# marbles_v70.net
KiCad netlist of a schematic drawn in EAGLE
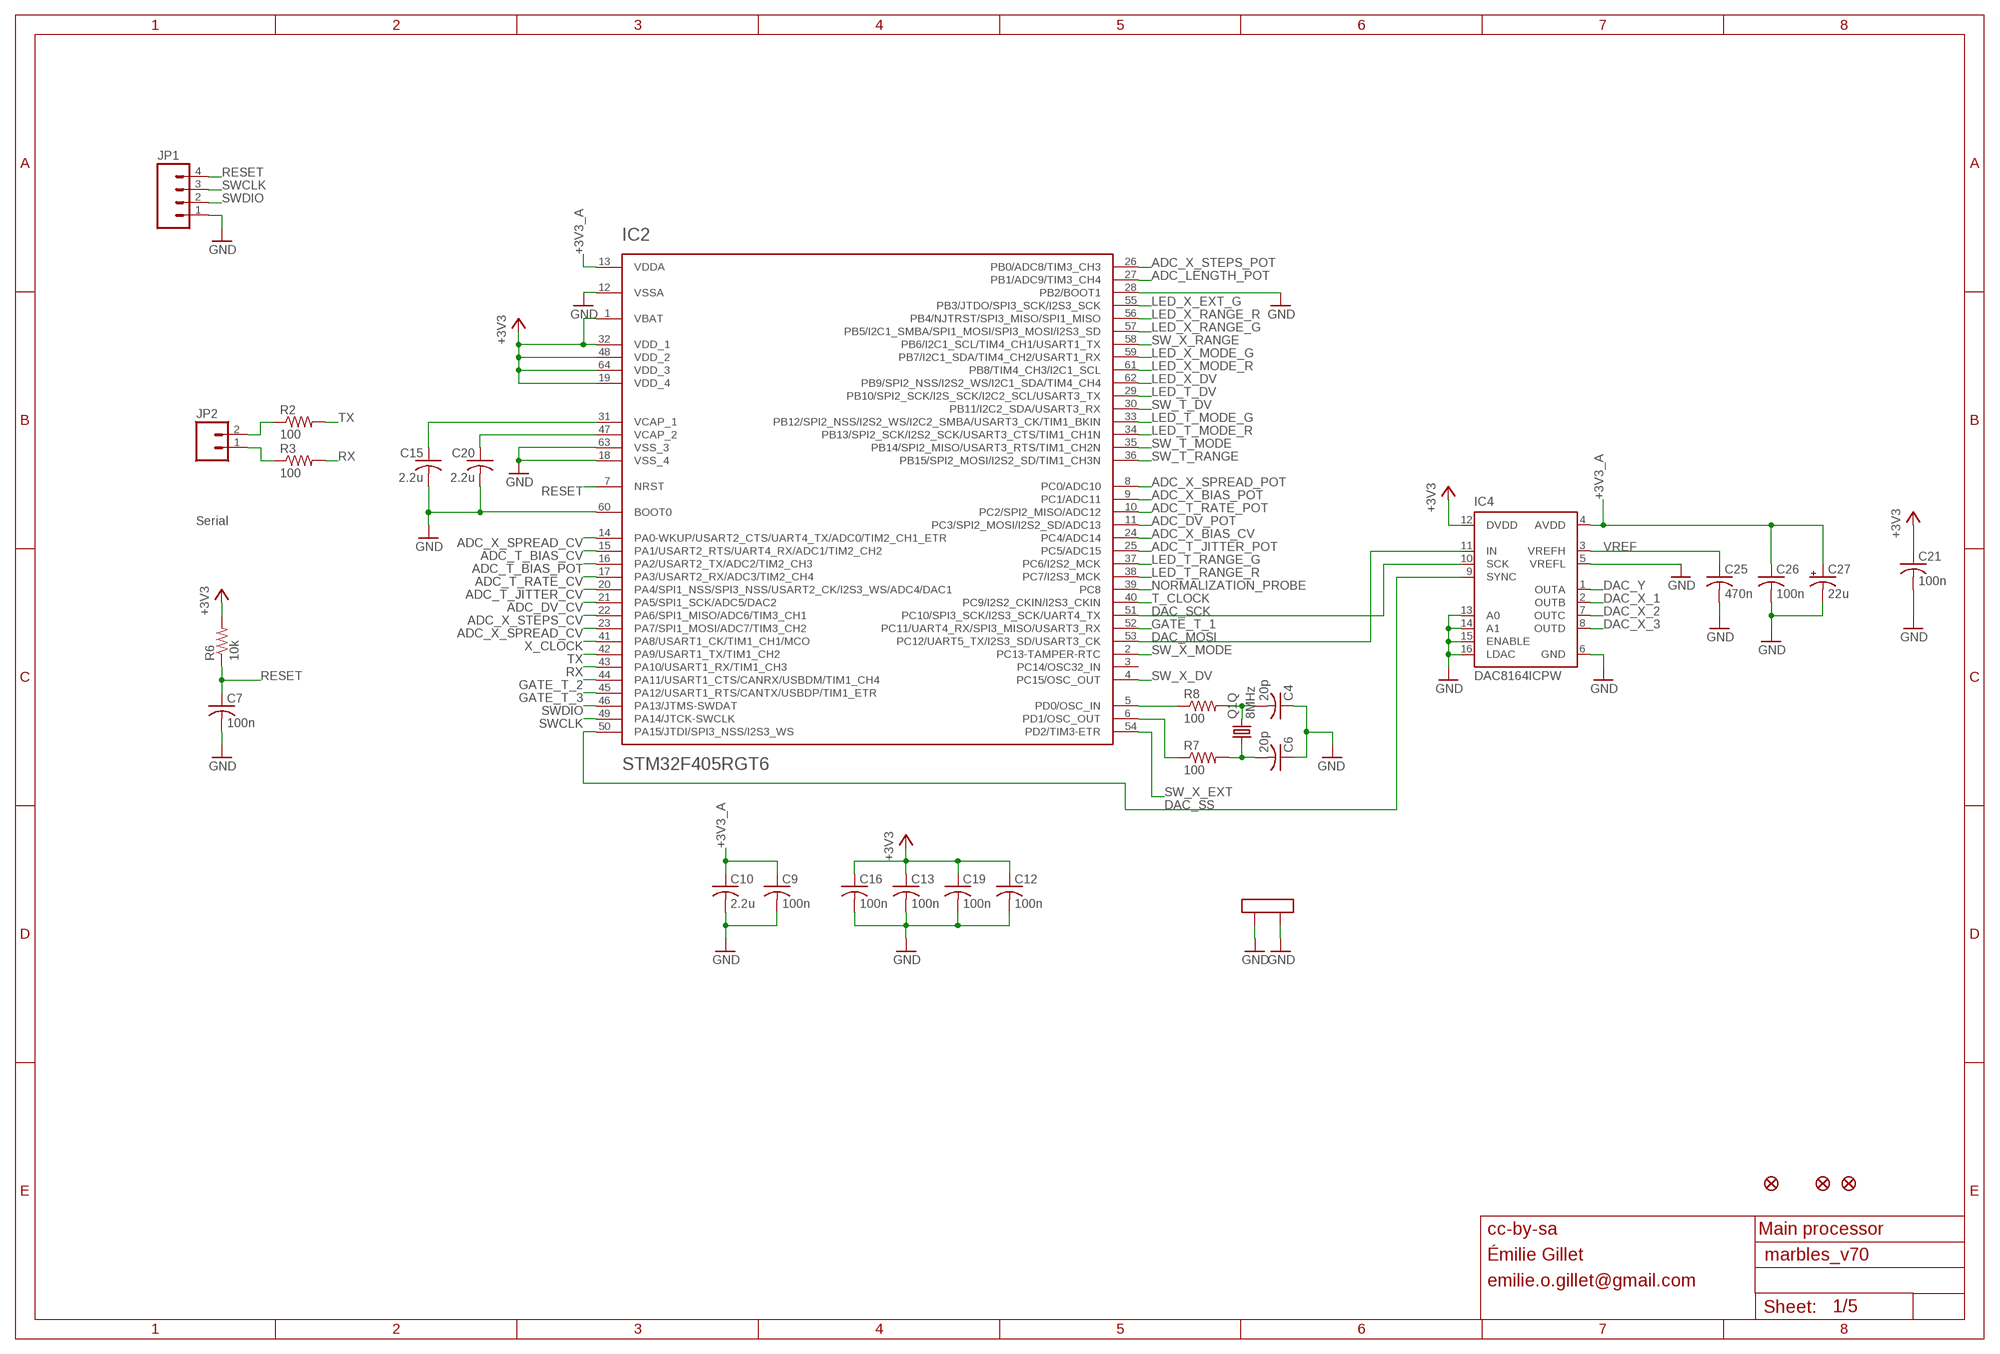
[diagram p0: schematic, sheet 1]
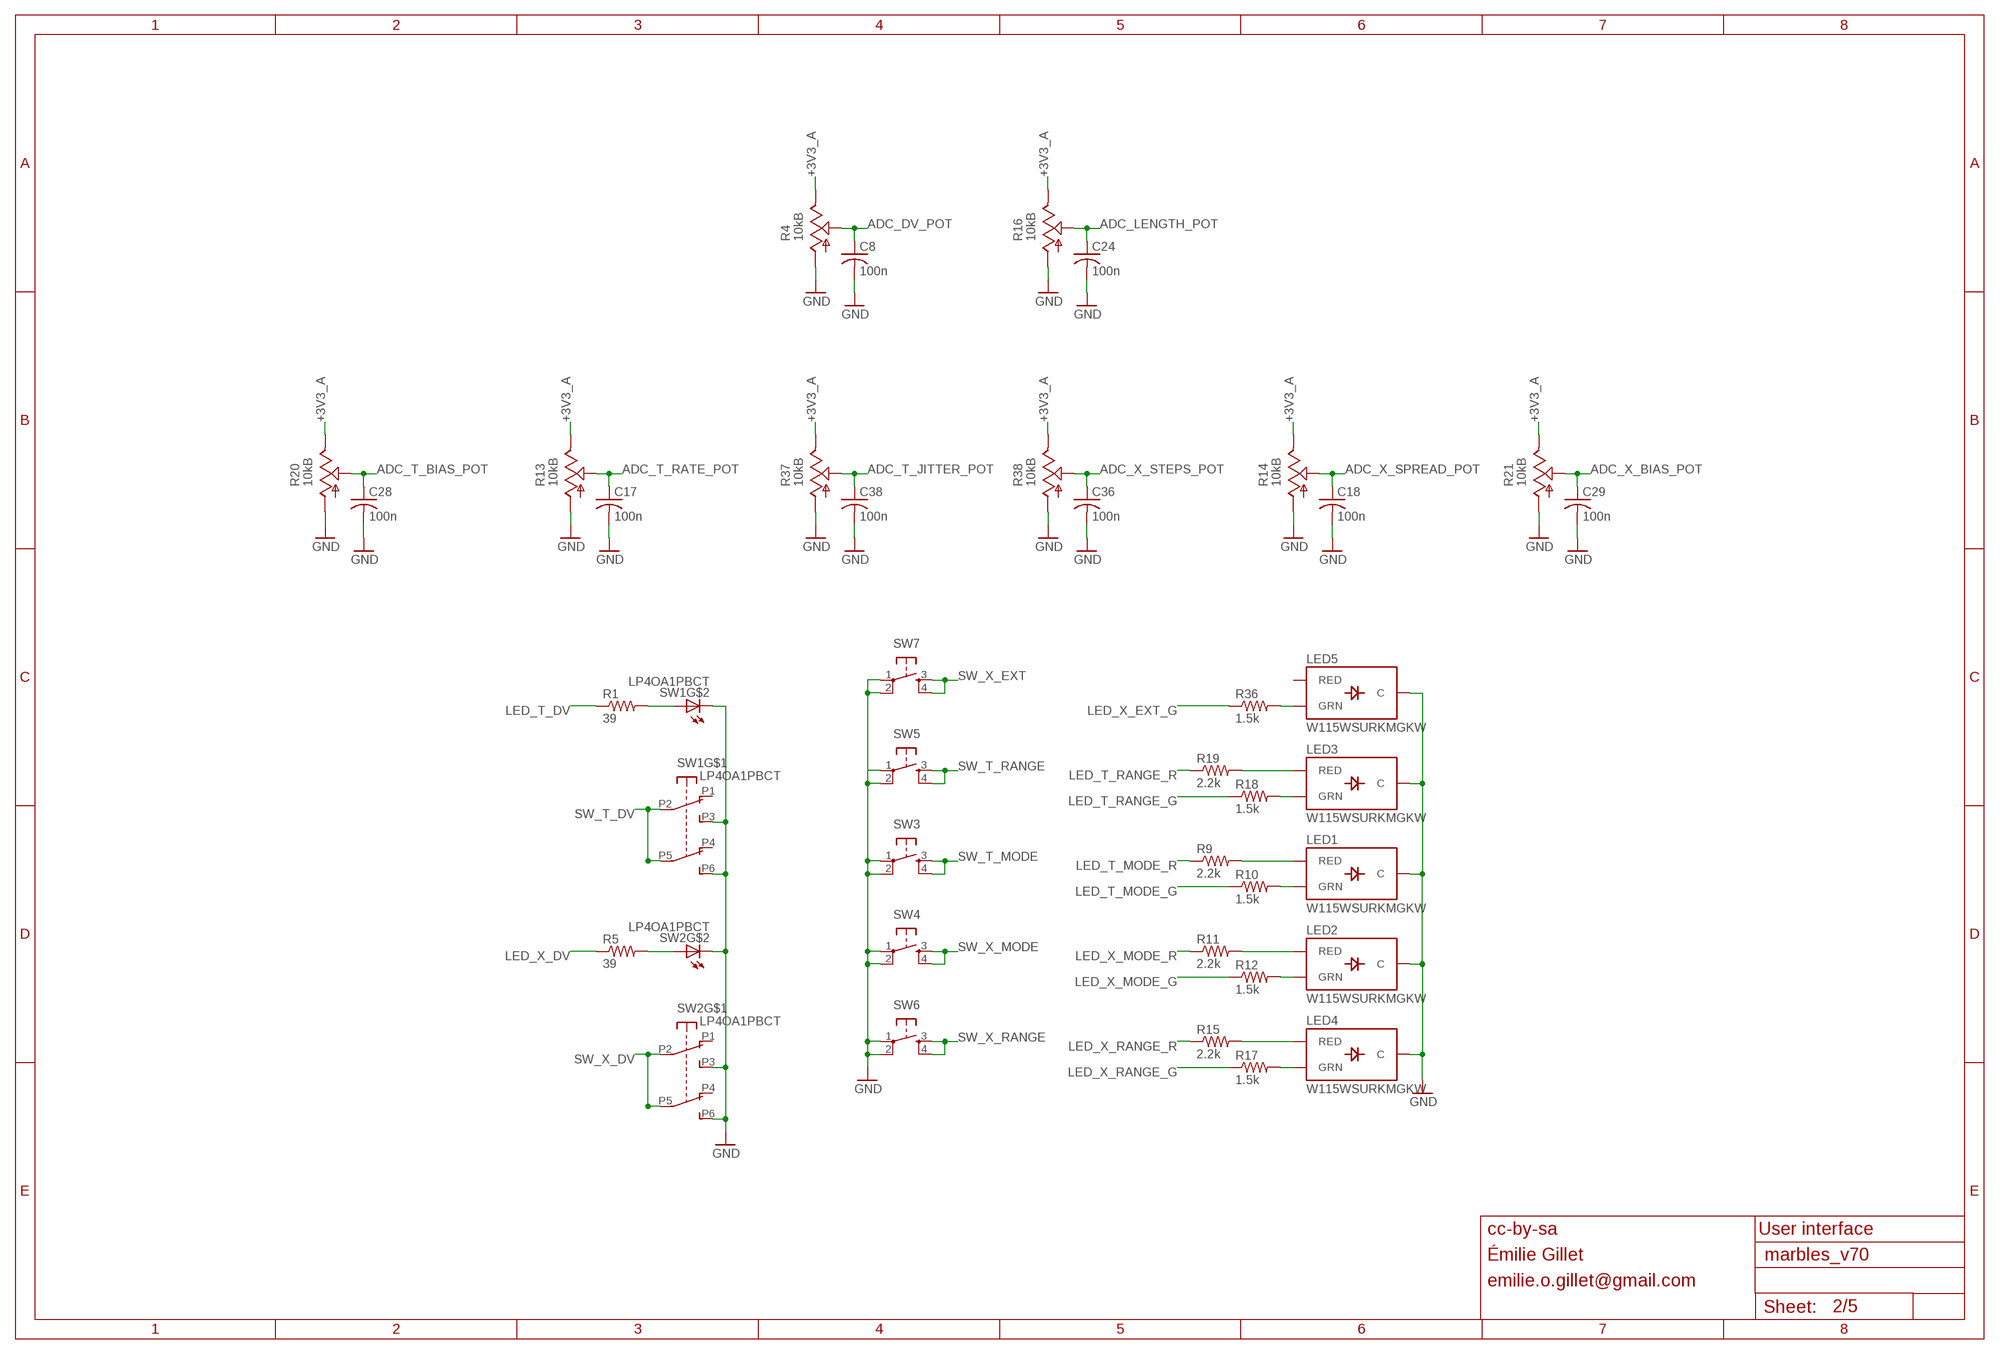
[diagram p1: schematic, sheet 2]
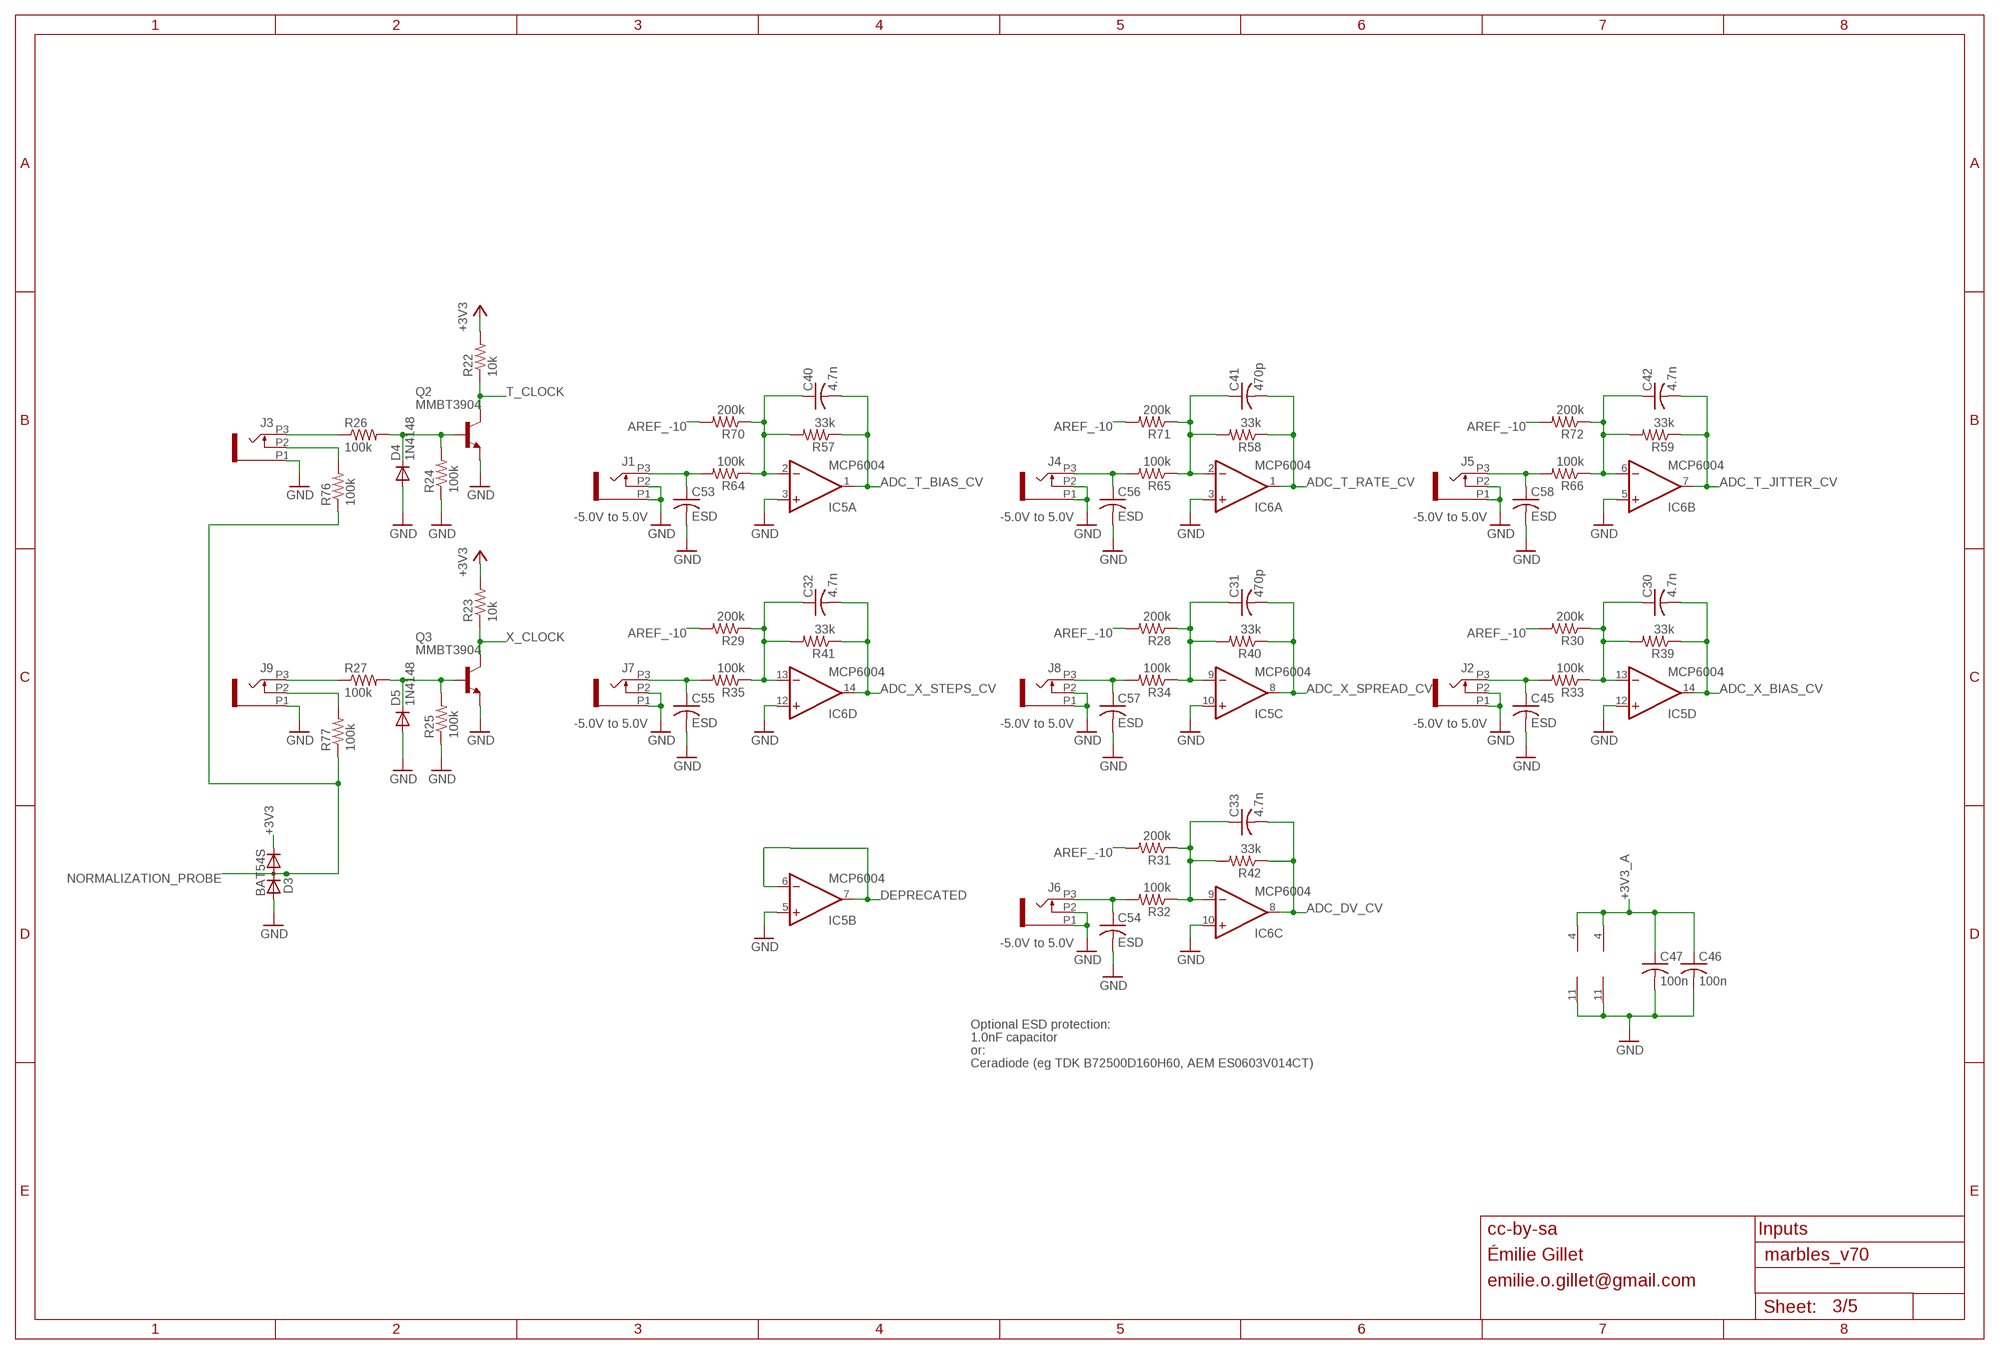
[diagram p2: schematic, sheet 3]
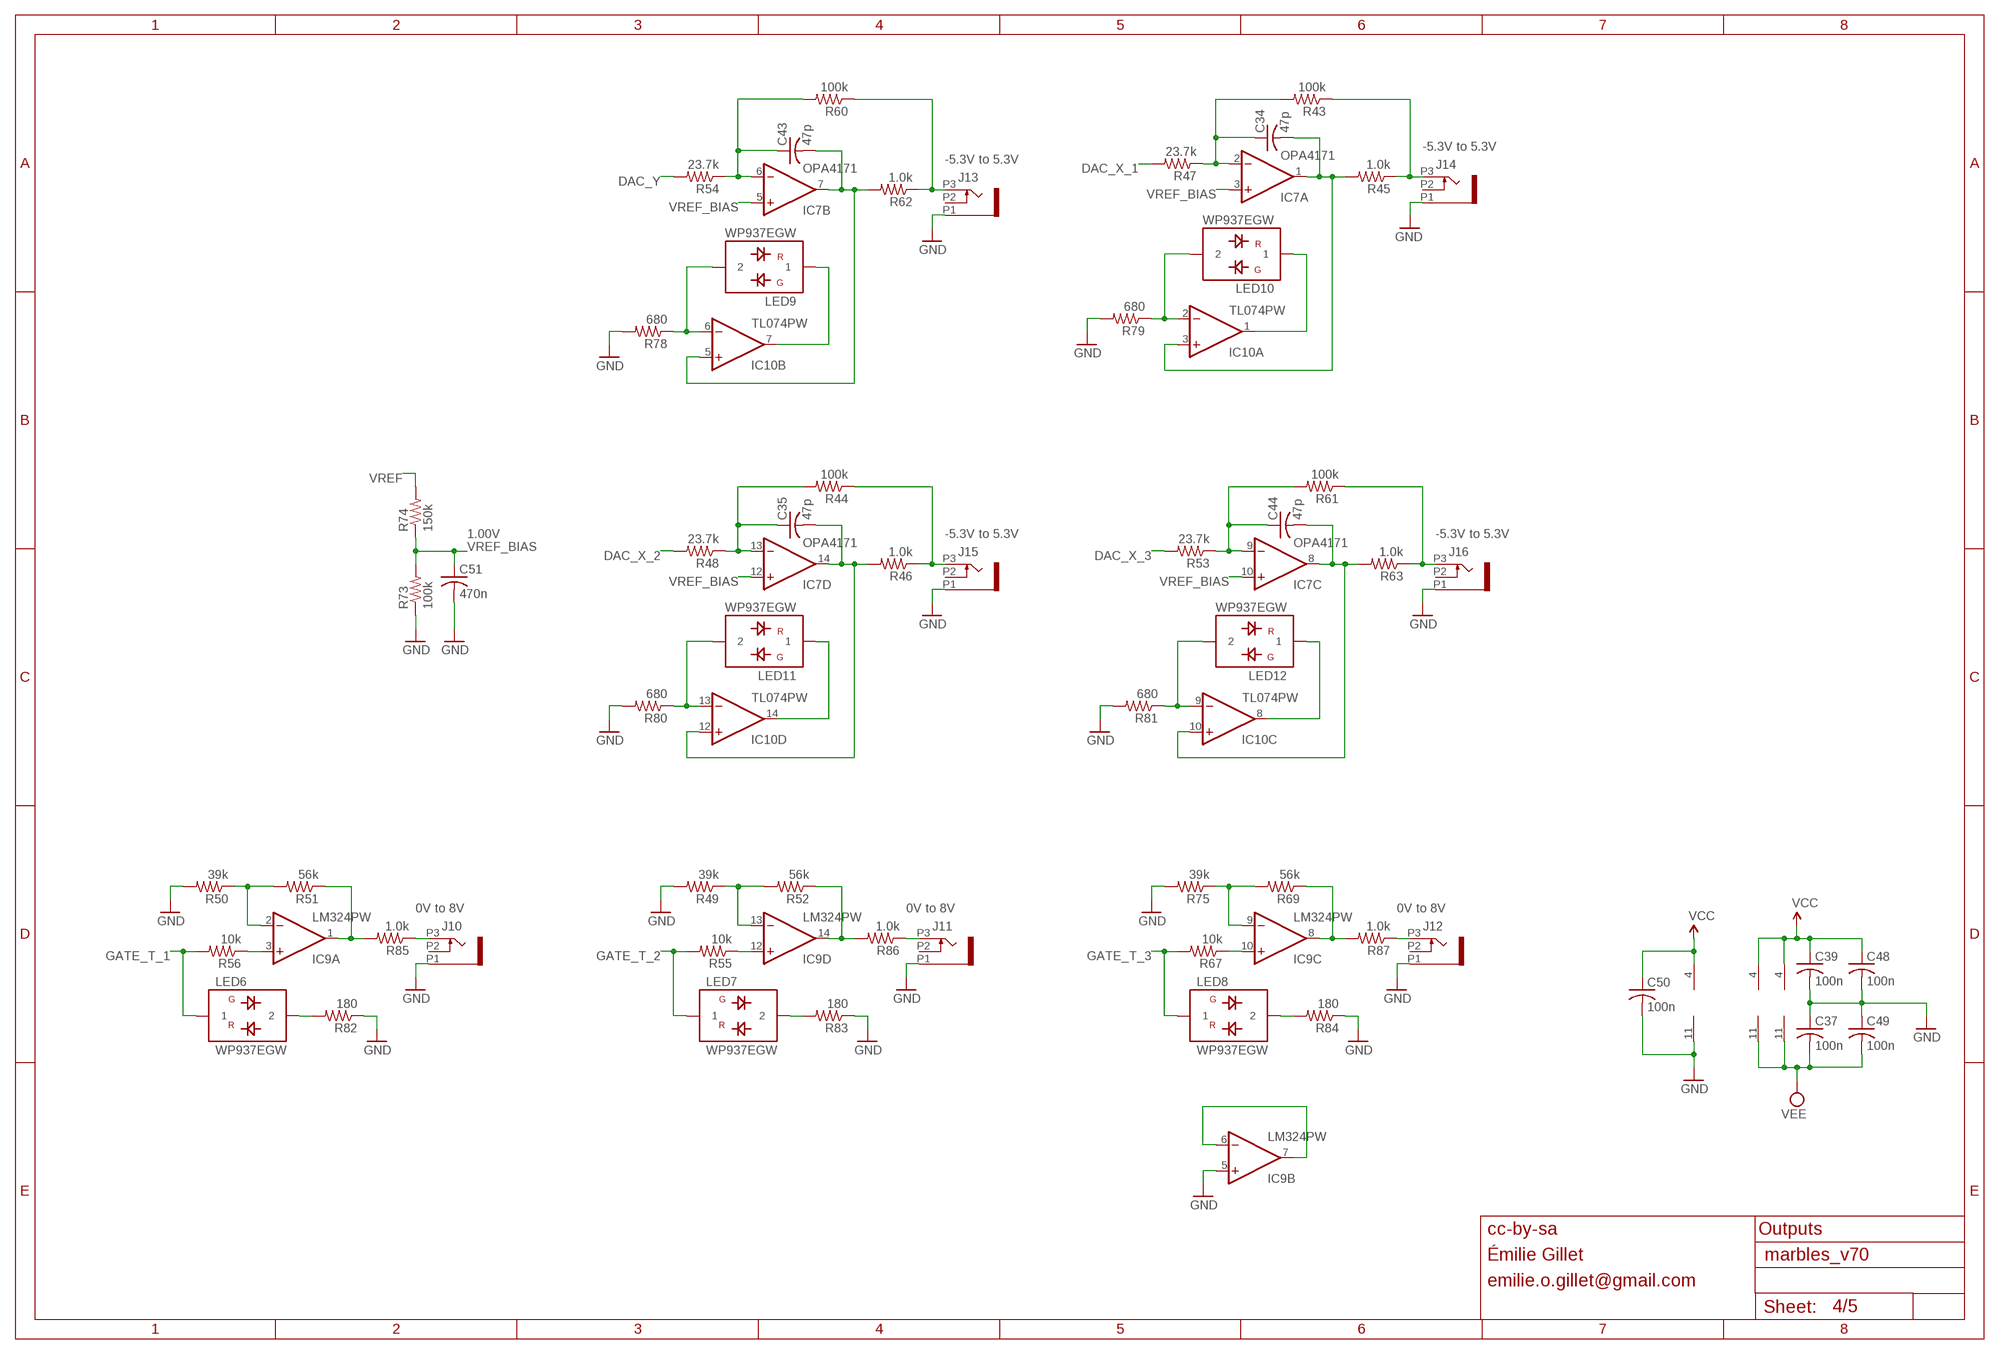
[diagram p3: schematic, sheet 4]
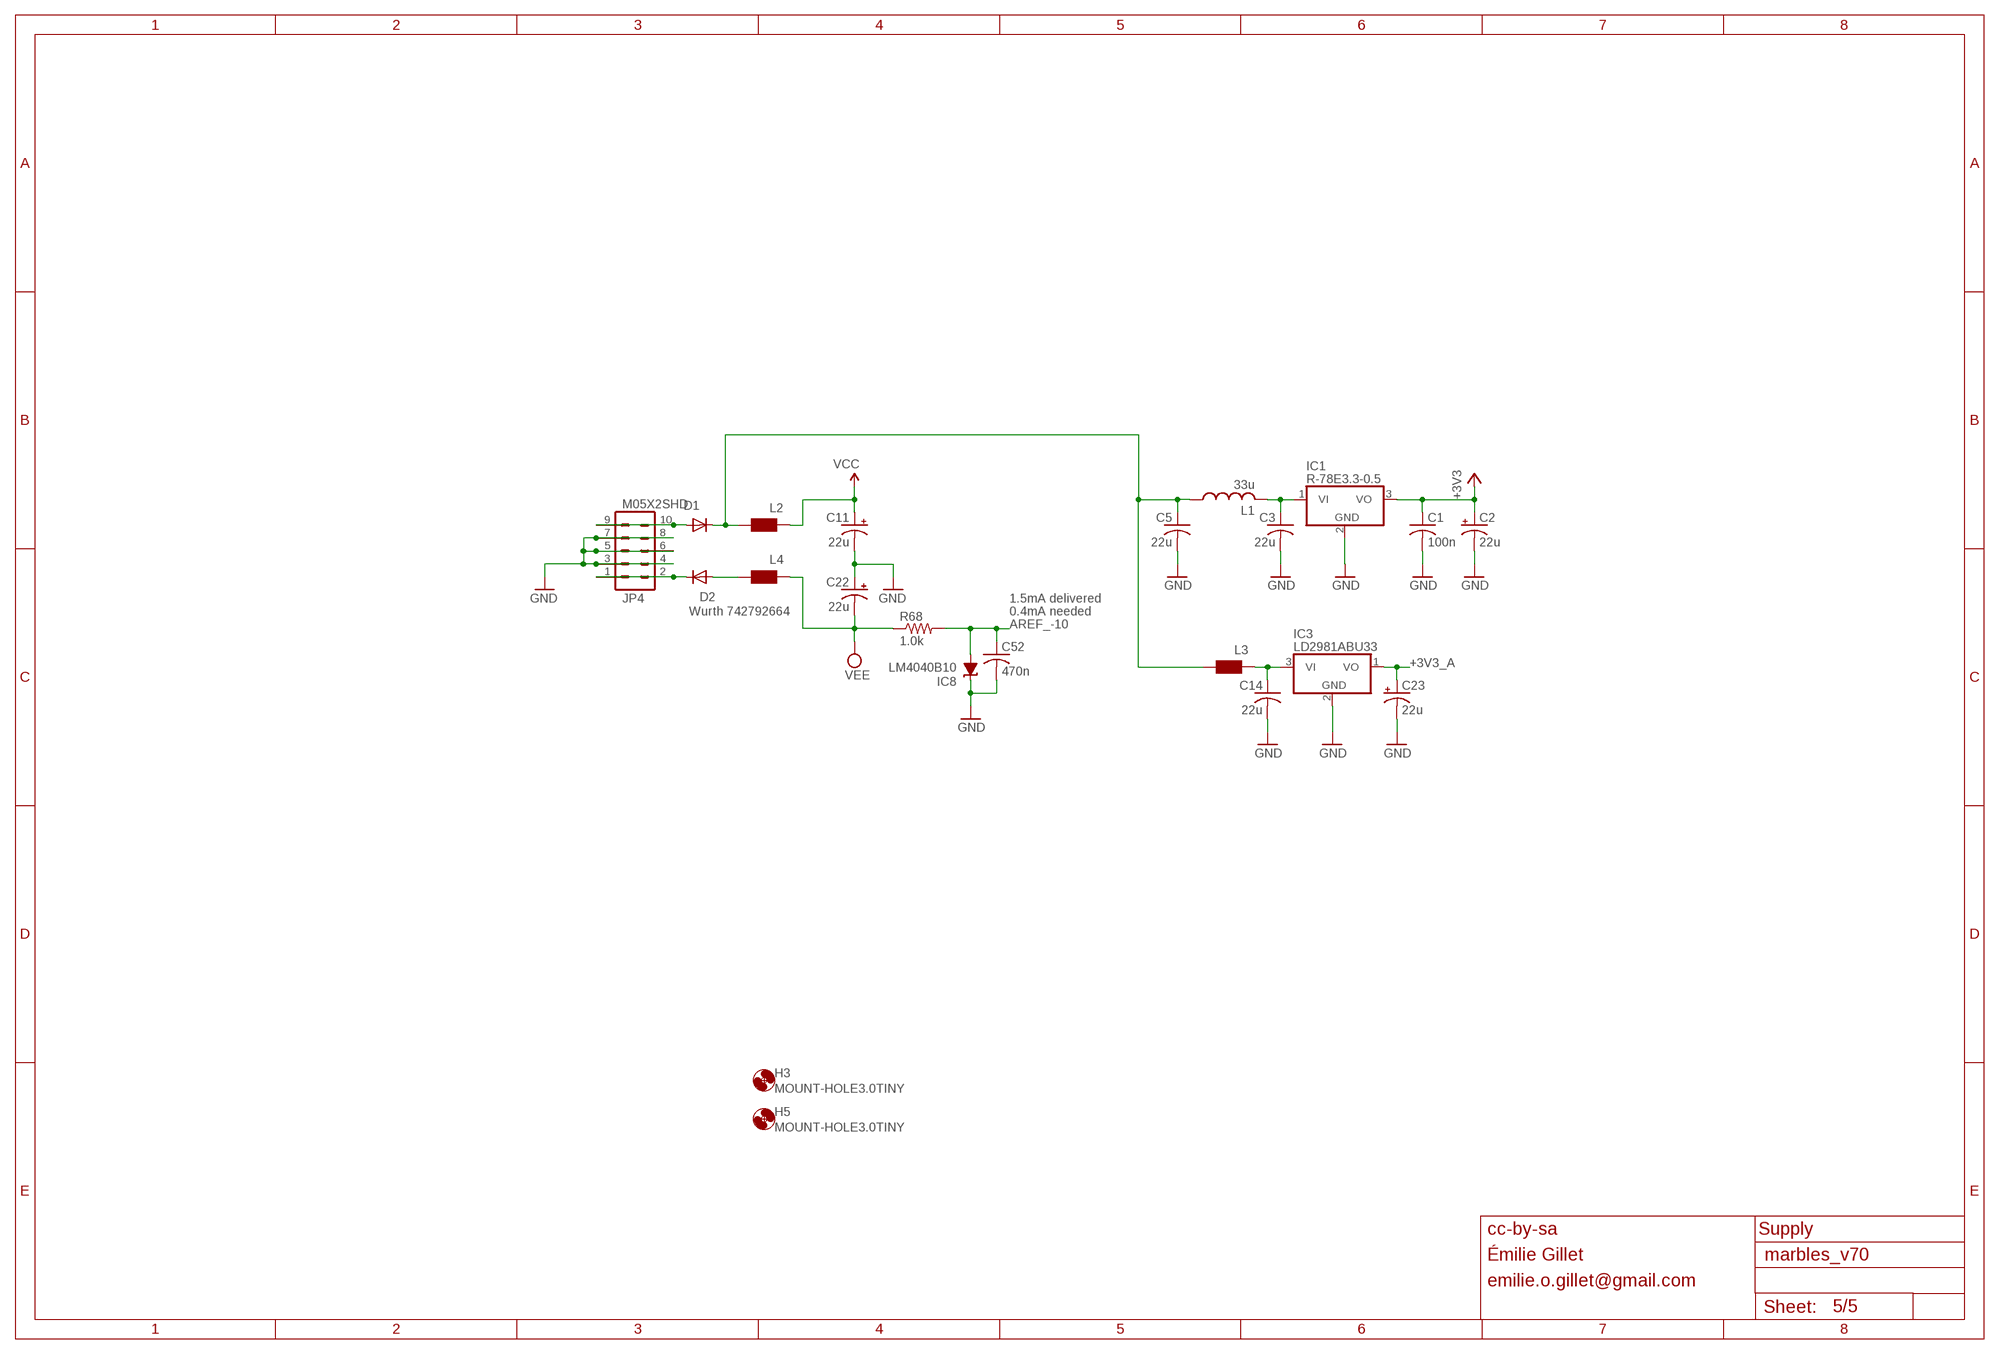
[diagram p4: schematic, sheet 5]

(export (version "E")
  (design (tool "Eeschema 10.0.6"))
  (components
    (comp (ref "C1")
      (value "100n")
      (footprint "eagle-import:C0603")
      (libsource (lib "eagle-import") (part "C-USC0603"))
    )
    (comp (ref "C2")
      (value "22u")
      (footprint "eagle-import:PANASONIC_C")
      (libsource (lib "eagle-import") (part "CPOL-USC"))
    )
    (comp (ref "C3")
      (value "22u")
      (footprint "eagle-import:C1206")
      (libsource (lib "eagle-import") (part "C-USC1206"))
    )
    (comp (ref "C5")
      (value "22u")
      (footprint "eagle-import:C1206")
      (libsource (lib "eagle-import") (part "C-USC1206"))
    )
    (comp (ref "C11")
      (value "22u")
      (footprint "eagle-import:PANASONIC_C")
      (libsource (lib "eagle-import") (part "CPOL-USC"))
    )
    (comp (ref "C14")
      (value "22u")
      (footprint "eagle-import:C1206")
      (libsource (lib "eagle-import") (part "C-USC1206"))
    )
    (comp (ref "C22")
      (value "22u")
      (footprint "eagle-import:PANASONIC_C")
      (libsource (lib "eagle-import") (part "CPOL-USC"))
    )
    (comp (ref "C23")
      (value "22u")
      (footprint "eagle-import:PANASONIC_C")
      (libsource (lib "eagle-import") (part "CPOL-USC"))
    )
    (comp (ref "C52")
      (value "470n")
      (footprint "eagle-import:C0603")
      (libsource (lib "eagle-import") (part "C-USC0603"))
    )
    (comp (ref "D1")
      (value "1N5819HW")
      (footprint "eagle-import:SOD123")
      (libsource (lib "eagle-import") (part "DIODE-SOD123"))
    )
    (comp (ref "D2")
      (value "1N5819HW")
      (footprint "eagle-import:SOD123")
      (libsource (lib "eagle-import") (part "DIODE-SOD123"))
    )
    (comp (ref "H3")
      (value "MOUNT-HOLE3.0TINY")
      (footprint "eagle-import:3,0TINY")
      (libsource (lib "eagle-import") (part "MOUNT-HOLE3.0TINY"))
    )
    (comp (ref "H5")
      (value "MOUNT-HOLE3.0TINY")
      (footprint "eagle-import:3,0TINY")
      (libsource (lib "eagle-import") (part "MOUNT-HOLE3.0TINY"))
    )
    (comp (ref "IC1")
      (value "R-78E3.3-0.5")
      (footprint "eagle-import:WE78")
      (libsource (lib "eagle-import") (part "WE173950378"))
    )
    (comp (ref "IC3")
      (value "LD2981ABU33")
      (footprint "eagle-import:SOT89")
      (libsource (lib "eagle-import") (part "LD2981ABU"))
    )
    (comp (ref "IC8")
      (value "LM4040B10")
      (footprint "eagle-import:DBZ_R-PDSO-G3")
      (libsource (lib "eagle-import") (part "LM4041DBZB12"))
    )
    (comp (ref "JP4")
      (value "M05X2SHD")
      (footprint "eagle-import:2X5-SHROUDED")
      (libsource (lib "eagle-import") (part "M05X2SHD"))
    )
    (comp (ref "L1")
      (value "33u")
      (footprint "eagle-import:L2012C")
      (libsource (lib "eagle-import") (part "L-USL2012C"))
    )
    (comp (ref "L2")
      (value "WE-CBF_0603")
      (footprint "eagle-import:0603")
      (libsource (lib "eagle-import") (part "WE-CBF_0603"))
    )
    (comp (ref "L3")
      (value "WE-CBF_0603")
      (footprint "eagle-import:0603")
      (libsource (lib "eagle-import") (part "WE-CBF_0603"))
    )
    (comp (ref "L4")
      (value "WE-CBF_0603")
      (footprint "eagle-import:0603")
      (libsource (lib "eagle-import") (part "WE-CBF_0603"))
    )
    (comp (ref "R68")
      (value "1.0k")
      (footprint "eagle-import:R0603")
      (libsource (lib "eagle-import") (part "R-US_R0603"))
    )
    (comp (ref "C4")
      (value "20p")
      (footprint "eagle-import:C0603")
      (libsource (lib "eagle-import") (part "C-USC0603"))
    )
    (comp (ref "C6")
      (value "20p")
      (footprint "eagle-import:C0603")
      (libsource (lib "eagle-import") (part "C-USC0603"))
    )
    (comp (ref "C7")
      (value "100n")
      (footprint "eagle-import:C0603")
      (libsource (lib "eagle-import") (part "C-USC0603"))
    )
    (comp (ref "C9")
      (value "100n")
      (footprint "eagle-import:C0603")
      (libsource (lib "eagle-import") (part "C-USC0603"))
    )
    (comp (ref "C10")
      (value "2.2u")
      (footprint "eagle-import:C0805")
      (libsource (lib "eagle-import") (part "C-USC0805"))
    )
    (comp (ref "C12")
      (value "100n")
      (footprint "eagle-import:C0603")
      (libsource (lib "eagle-import") (part "C-USC0603"))
    )
    (comp (ref "C13")
      (value "100n")
      (footprint "eagle-import:C0603")
      (libsource (lib "eagle-import") (part "C-USC0603"))
    )
    (comp (ref "C15")
      (value "2.2u")
      (footprint "eagle-import:C0805")
      (libsource (lib "eagle-import") (part "C-USC0805"))
    )
    (comp (ref "C16")
      (value "100n")
      (footprint "eagle-import:C0603")
      (libsource (lib "eagle-import") (part "C-USC0603"))
    )
    (comp (ref "C19")
      (value "100n")
      (footprint "eagle-import:C0603")
      (libsource (lib "eagle-import") (part "C-USC0603"))
    )
    (comp (ref "C20")
      (value "2.2u")
      (footprint "eagle-import:C0805")
      (libsource (lib "eagle-import") (part "C-USC0805"))
    )
    (comp (ref "C21")
      (value "100n")
      (footprint "eagle-import:C0603")
      (libsource (lib "eagle-import") (part "C-USC0603"))
    )
    (comp (ref "C25")
      (value "470n")
      (footprint "eagle-import:C0603")
      (libsource (lib "eagle-import") (part "C-USC0603"))
    )
    (comp (ref "C26")
      (value "100n")
      (footprint "eagle-import:C0603")
      (libsource (lib "eagle-import") (part "C-USC0603"))
    )
    (comp (ref "C27")
      (value "22u")
      (footprint "eagle-import:PANASONIC_C")
      (libsource (lib "eagle-import") (part "CPOL-USC"))
    )
    (comp (ref "F1")
      (value "FIDUCIAL1X2")
      (footprint "eagle-import:FIDUCIAL-1X2")
      (libsource (lib "eagle-import") (part "FIDUCIAL1X2"))
    )
    (comp (ref "F2")
      (value "FIDUCIAL1X2")
      (footprint "eagle-import:FIDUCIAL-1X2")
      (libsource (lib "eagle-import") (part "FIDUCIAL1X2"))
    )
    (comp (ref "F3")
      (value "FIDUCIAL1X2")
      (footprint "eagle-import:FIDUCIAL-1X2")
      (libsource (lib "eagle-import") (part "FIDUCIAL1X2"))
    )
    (comp (ref "IC2")
      (value "STM32F405RGT6")
      (footprint "eagle-import:TQFP-10X10-64")
      (libsource (lib "eagle-import") (part "STM32F20X"))
    )
    (comp (ref "IC4")
      (value "DAC8164ICPW")
      (footprint "eagle-import:SOP65P640X110-16N")
      (libsource (lib "eagle-import") (part "DAC8564"))
    )
    (comp (ref "JP1")
      (value "M04PTH")
      (footprint "eagle-import:1X04")
      (libsource (lib "eagle-import") (part "M04PTH"))
    )
    (comp (ref "JP2")
      (value "M02PTH")
      (footprint "eagle-import:1X02")
      (libsource (lib "eagle-import") (part "M02PTH"))
    )
    (comp (ref "Q1")
      (value "8MHz")
      (footprint "eagle-import:CTS406")
      (libsource (lib "eagle-import") (part "CRYSTAL"))
    )
    (comp (ref "R2")
      (value "100")
      (footprint "eagle-import:R0603")
      (libsource (lib "eagle-import") (part "R-US_R0603"))
    )
    (comp (ref "R3")
      (value "100")
      (footprint "eagle-import:R0603")
      (libsource (lib "eagle-import") (part "R-US_R0603"))
    )
    (comp (ref "R6")
      (value "10k")
      (footprint "eagle-import:R0603")
      (libsource (lib "eagle-import") (part "R-US_R0603"))
    )
    (comp (ref "R7")
      (value "100")
      (footprint "eagle-import:R0603")
      (libsource (lib "eagle-import") (part "R-US_R0603"))
    )
    (comp (ref "R8")
      (value "100")
      (footprint "eagle-import:R0603")
      (libsource (lib "eagle-import") (part "R-US_R0603"))
    )
    (comp (ref "C34")
      (value "47p")
      (footprint "eagle-import:C0603")
      (libsource (lib "eagle-import") (part "C-USC0603"))
    )
    (comp (ref "C35")
      (value "47p")
      (footprint "eagle-import:C0603")
      (libsource (lib "eagle-import") (part "C-USC0603"))
    )
    (comp (ref "C37")
      (value "100n")
      (footprint "eagle-import:C0603")
      (libsource (lib "eagle-import") (part "C-USC0603"))
    )
    (comp (ref "C39")
      (value "100n")
      (footprint "eagle-import:C0603")
      (libsource (lib "eagle-import") (part "C-USC0603"))
    )
    (comp (ref "C43")
      (value "47p")
      (footprint "eagle-import:C0603")
      (libsource (lib "eagle-import") (part "C-USC0603"))
    )
    (comp (ref "C44")
      (value "47p")
      (footprint "eagle-import:C0603")
      (libsource (lib "eagle-import") (part "C-USC0603"))
    )
    (comp (ref "C48")
      (value "100n")
      (footprint "eagle-import:C0603")
      (libsource (lib "eagle-import") (part "C-USC0603"))
    )
    (comp (ref "C49")
      (value "100n")
      (footprint "eagle-import:C0603")
      (libsource (lib "eagle-import") (part "C-USC0603"))
    )
    (comp (ref "C50")
      (value "100n")
      (footprint "eagle-import:C0603")
      (libsource (lib "eagle-import") (part "C-USC0603"))
    )
    (comp (ref "C51")
      (value "470n")
      (footprint "eagle-import:C0603")
      (libsource (lib "eagle-import") (part "C-USC0603"))
    )
    (comp (ref "IC7")
      (value "OPA4171")
      (footprint "eagle-import:TSSOP14_065")
      (libsource (lib "eagle-import") (part "TL074PW"))
    )
    (comp (ref "IC9")
      (value "LM324PW")
      (footprint "eagle-import:TSSOP14_065")
      (libsource (lib "eagle-import") (part "TL074PW"))
    )
    (comp (ref "IC10")
      (value "TL074PW")
      (footprint "eagle-import:TSSOP14_065")
      (libsource (lib "eagle-import") (part "TL074PW"))
    )
    (comp (ref "J10")
      (value "PJ301_THONKICONN6")
      (footprint "eagle-import:WQP_PJ_301M6")
      (libsource (lib "eagle-import") (part "PJ301_THONKICONN6"))
    )
    (comp (ref "J11")
      (value "PJ301_THONKICONN6")
      (footprint "eagle-import:WQP_PJ_301M6")
      (libsource (lib "eagle-import") (part "PJ301_THONKICONN6"))
    )
    (comp (ref "J12")
      (value "PJ301_THONKICONN6")
      (footprint "eagle-import:WQP_PJ_301M6")
      (libsource (lib "eagle-import") (part "PJ301_THONKICONN6"))
    )
    (comp (ref "J13")
      (value "PJ301_THONKICONN6")
      (footprint "eagle-import:WQP_PJ_301M6")
      (libsource (lib "eagle-import") (part "PJ301_THONKICONN6"))
    )
    (comp (ref "J14")
      (value "PJ301_THONKICONN6")
      (footprint "eagle-import:WQP_PJ_301M6")
      (libsource (lib "eagle-import") (part "PJ301_THONKICONN6"))
    )
    (comp (ref "J15")
      (value "PJ301_THONKICONN6")
      (footprint "eagle-import:WQP_PJ_301M6")
      (libsource (lib "eagle-import") (part "PJ301_THONKICONN6"))
    )
    (comp (ref "J16")
      (value "PJ301_THONKICONN6")
      (footprint "eagle-import:WQP_PJ_301M6")
      (libsource (lib "eagle-import") (part "PJ301_THONKICONN6"))
    )
    (comp (ref "LED6")
      (value "WP937EGW")
      (footprint "eagle-import:LED3MM")
      (libsource (lib "eagle-import") (part "LED-BICOLOR-SHARED-THROUGHHOLE"))
    )
    (comp (ref "LED7")
      (value "WP937EGW")
      (footprint "eagle-import:LED3MM")
      (libsource (lib "eagle-import") (part "LED-BICOLOR-SHARED-THROUGHHOLE"))
    )
    (comp (ref "LED8")
      (value "WP937EGW")
      (footprint "eagle-import:LED3MM")
      (libsource (lib "eagle-import") (part "LED-BICOLOR-SHARED-THROUGHHOLE"))
    )
    (comp (ref "LED9")
      (value "WP937EGW")
      (footprint "eagle-import:LED3MM")
      (libsource (lib "eagle-import") (part "LED-BICOLOR-SHARED-THROUGHHOLE"))
    )
    (comp (ref "LED10")
      (value "WP937EGW")
      (footprint "eagle-import:LED3MM")
      (libsource (lib "eagle-import") (part "LED-BICOLOR-SHARED-THROUGHHOLE"))
    )
    (comp (ref "LED11")
      (value "WP937EGW")
      (footprint "eagle-import:LED3MM")
      (libsource (lib "eagle-import") (part "LED-BICOLOR-SHARED-THROUGHHOLE"))
    )
    (comp (ref "LED12")
      (value "WP937EGW")
      (footprint "eagle-import:LED3MM")
      (libsource (lib "eagle-import") (part "LED-BICOLOR-SHARED-THROUGHHOLE"))
    )
    (comp (ref "R43")
      (value "100k")
      (footprint "eagle-import:R0603")
      (libsource (lib "eagle-import") (part "R-US_R0603"))
    )
    (comp (ref "R44")
      (value "100k")
      (footprint "eagle-import:R0603")
      (libsource (lib "eagle-import") (part "R-US_R0603"))
    )
    (comp (ref "R45")
      (value "1.0k")
      (footprint "eagle-import:R0603")
      (libsource (lib "eagle-import") (part "R-US_R0603"))
    )
    (comp (ref "R46")
      (value "1.0k")
      (footprint "eagle-import:R0603")
      (libsource (lib "eagle-import") (part "R-US_R0603"))
    )
    (comp (ref "R47")
      (value "23.7k")
      (footprint "eagle-import:R0603")
      (libsource (lib "eagle-import") (part "R-US_R0603"))
    )
    (comp (ref "R48")
      (value "23.7k")
      (footprint "eagle-import:R0603")
      (libsource (lib "eagle-import") (part "R-US_R0603"))
    )
    (comp (ref "R49")
      (value "39k")
      (footprint "eagle-import:R0603")
      (libsource (lib "eagle-import") (part "R-US_R0603"))
    )
    (comp (ref "R50")
      (value "39k")
      (footprint "eagle-import:R0603")
      (libsource (lib "eagle-import") (part "R-US_R0603"))
    )
    (comp (ref "R51")
      (value "56k")
      (footprint "eagle-import:R0603")
      (libsource (lib "eagle-import") (part "R-US_R0603"))
    )
    (comp (ref "R52")
      (value "56k")
      (footprint "eagle-import:R0603")
      (libsource (lib "eagle-import") (part "R-US_R0603"))
    )
    (comp (ref "R53")
      (value "23.7k")
      (footprint "eagle-import:R0603")
      (libsource (lib "eagle-import") (part "R-US_R0603"))
    )
    (comp (ref "R54")
      (value "23.7k")
      (footprint "eagle-import:R0603")
      (libsource (lib "eagle-import") (part "R-US_R0603"))
    )
    (comp (ref "R55")
      (value "10k")
      (footprint "eagle-import:R0603")
      (libsource (lib "eagle-import") (part "R-US_R0603"))
    )
    (comp (ref "R56")
      (value "10k")
      (footprint "eagle-import:R0603")
      (libsource (lib "eagle-import") (part "R-US_R0603"))
    )
    (comp (ref "R60")
      (value "100k")
      (footprint "eagle-import:R0603")
      (libsource (lib "eagle-import") (part "R-US_R0603"))
    )
    (comp (ref "R61")
      (value "100k")
      (footprint "eagle-import:R0603")
      (libsource (lib "eagle-import") (part "R-US_R0603"))
    )
    (comp (ref "R62")
      (value "1.0k")
      (footprint "eagle-import:R0603")
      (libsource (lib "eagle-import") (part "R-US_R0603"))
    )
    (comp (ref "R63")
      (value "1.0k")
      (footprint "eagle-import:R0603")
      (libsource (lib "eagle-import") (part "R-US_R0603"))
    )
    (comp (ref "R67")
      (value "10k")
      (footprint "eagle-import:R0603")
      (libsource (lib "eagle-import") (part "R-US_R0603"))
    )
    (comp (ref "R69")
      (value "56k")
      (footprint "eagle-import:R0603")
      (libsource (lib "eagle-import") (part "R-US_R0603"))
    )
    (comp (ref "R73")
      (value "100k")
      (footprint "eagle-import:R0603")
      (libsource (lib "eagle-import") (part "R-US_R0603"))
    )
    (comp (ref "R74")
      (value "150k")
      (footprint "eagle-import:R0603")
      (libsource (lib "eagle-import") (part "R-US_R0603"))
    )
    (comp (ref "R75")
      (value "39k")
      (footprint "eagle-import:R0603")
      (libsource (lib "eagle-import") (part "R-US_R0603"))
    )
    (comp (ref "R78")
      (value "680")
      (footprint "eagle-import:R0603")
      (libsource (lib "eagle-import") (part "R-US_R0603"))
    )
    (comp (ref "R79")
      (value "680")
      (footprint "eagle-import:R0603")
      (libsource (lib "eagle-import") (part "R-US_R0603"))
    )
    (comp (ref "R80")
      (value "680")
      (footprint "eagle-import:R0603")
      (libsource (lib "eagle-import") (part "R-US_R0603"))
    )
    (comp (ref "R81")
      (value "680")
      (footprint "eagle-import:R0603")
      (libsource (lib "eagle-import") (part "R-US_R0603"))
    )
    (comp (ref "R82")
      (value "180")
      (footprint "eagle-import:R0603")
      (libsource (lib "eagle-import") (part "R-US_R0603"))
    )
    (comp (ref "R83")
      (value "180")
      (footprint "eagle-import:R0603")
      (libsource (lib "eagle-import") (part "R-US_R0603"))
    )
    (comp (ref "R84")
      (value "180")
      (footprint "eagle-import:R0603")
      (libsource (lib "eagle-import") (part "R-US_R0603"))
    )
    (comp (ref "R85")
      (value "1.0k")
      (footprint "eagle-import:R0603")
      (libsource (lib "eagle-import") (part "R-US_R0603"))
    )
    (comp (ref "R86")
      (value "1.0k")
      (footprint "eagle-import:R0603")
      (libsource (lib "eagle-import") (part "R-US_R0603"))
    )
    (comp (ref "R87")
      (value "1.0k")
      (footprint "eagle-import:R0603")
      (libsource (lib "eagle-import") (part "R-US_R0603"))
    )
    (comp (ref "C30")
      (value "4.7n")
      (footprint "eagle-import:C0603")
      (libsource (lib "eagle-import") (part "C-USC0603"))
    )
    (comp (ref "C31")
      (value "470p")
      (footprint "eagle-import:C0603")
      (libsource (lib "eagle-import") (part "C-USC0603"))
    )
    (comp (ref "C32")
      (value "4.7n")
      (footprint "eagle-import:C0603")
      (libsource (lib "eagle-import") (part "C-USC0603"))
    )
    (comp (ref "C33")
      (value "4.7n")
      (footprint "eagle-import:C0603")
      (libsource (lib "eagle-import") (part "C-USC0603"))
    )
    (comp (ref "C40")
      (value "4.7n")
      (footprint "eagle-import:C0603")
      (libsource (lib "eagle-import") (part "C-USC0603"))
    )
    (comp (ref "C41")
      (value "470p")
      (footprint "eagle-import:C0603")
      (libsource (lib "eagle-import") (part "C-USC0603"))
    )
    (comp (ref "C42")
      (value "4.7n")
      (footprint "eagle-import:C0603")
      (libsource (lib "eagle-import") (part "C-USC0603"))
    )
    (comp (ref "C45")
      (value "ESD")
      (footprint "eagle-import:C0603")
      (libsource (lib "eagle-import") (part "C-USC0603"))
    )
    (comp (ref "C46")
      (value "100n")
      (footprint "eagle-import:C0603")
      (libsource (lib "eagle-import") (part "C-USC0603"))
    )
    (comp (ref "C47")
      (value "100n")
      (footprint "eagle-import:C0603")
      (libsource (lib "eagle-import") (part "C-USC0603"))
    )
    (comp (ref "C53")
      (value "ESD")
      (footprint "eagle-import:C0603")
      (libsource (lib "eagle-import") (part "C-USC0603"))
    )
    (comp (ref "C54")
      (value "ESD")
      (footprint "eagle-import:C0603")
      (libsource (lib "eagle-import") (part "C-USC0603"))
    )
    (comp (ref "C55")
      (value "ESD")
      (footprint "eagle-import:C0603")
      (libsource (lib "eagle-import") (part "C-USC0603"))
    )
    (comp (ref "C56")
      (value "ESD")
      (footprint "eagle-import:C0603")
      (libsource (lib "eagle-import") (part "C-USC0603"))
    )
    (comp (ref "C57")
      (value "ESD")
      (footprint "eagle-import:C0603")
      (libsource (lib "eagle-import") (part "C-USC0603"))
    )
    (comp (ref "C58")
      (value "ESD")
      (footprint "eagle-import:C0603")
      (libsource (lib "eagle-import") (part "C-USC0603"))
    )
    (comp (ref "D3")
      (value "BAT54S")
      (footprint "eagle-import:SOT23")
      (libsource (lib "eagle-import") (part "DIODE_2CACA-SOT23"))
    )
    (comp (ref "D4")
      (value "1N4148")
      (footprint "eagle-import:SOD523")
      (libsource (lib "eagle-import") (part "DIODE-SOD523"))
    )
    (comp (ref "D5")
      (value "1N4148")
      (footprint "eagle-import:SOD523")
      (libsource (lib "eagle-import") (part "DIODE-SOD523"))
    )
    (comp (ref "IC5")
      (value "MCP6004")
      (footprint "eagle-import:TSSOP14_065")
      (libsource (lib "eagle-import") (part "TL074PW"))
    )
    (comp (ref "IC6")
      (value "MCP6004")
      (footprint "eagle-import:TSSOP14_065")
      (libsource (lib "eagle-import") (part "TL074PW"))
    )
    (comp (ref "J1")
      (value "PJ301_THONKICONN6")
      (footprint "eagle-import:WQP_PJ_301M6")
      (libsource (lib "eagle-import") (part "PJ301_THONKICONN6"))
    )
    (comp (ref "J2")
      (value "PJ301_THONKICONN6")
      (footprint "eagle-import:WQP_PJ_301M6")
      (libsource (lib "eagle-import") (part "PJ301_THONKICONN6"))
    )
    (comp (ref "J3")
      (value "PJ301_THONKICONN6")
      (footprint "eagle-import:WQP_PJ_301M6")
      (libsource (lib "eagle-import") (part "PJ301_THONKICONN6"))
    )
    (comp (ref "J4")
      (value "PJ301_THONKICONN6")
      (footprint "eagle-import:WQP_PJ_301M6")
      (libsource (lib "eagle-import") (part "PJ301_THONKICONN6"))
    )
    (comp (ref "J5")
      (value "PJ301_THONKICONN6")
      (footprint "eagle-import:WQP_PJ_301M6")
      (libsource (lib "eagle-import") (part "PJ301_THONKICONN6"))
    )
    (comp (ref "J6")
      (value "PJ301_THONKICONN6")
      (footprint "eagle-import:WQP_PJ_301M6")
      (libsource (lib "eagle-import") (part "PJ301_THONKICONN6"))
    )
    (comp (ref "J7")
      (value "PJ301_THONKICONN6")
      (footprint "eagle-import:WQP_PJ_301M6")
      (libsource (lib "eagle-import") (part "PJ301_THONKICONN6"))
    )
    (comp (ref "J8")
      (value "PJ301_THONKICONN6")
      (footprint "eagle-import:WQP_PJ_301M6")
      (libsource (lib "eagle-import") (part "PJ301_THONKICONN6"))
    )
    (comp (ref "J9")
      (value "PJ301_THONKICONN6")
      (footprint "eagle-import:WQP_PJ_301M6")
      (libsource (lib "eagle-import") (part "PJ301_THONKICONN6"))
    )
    (comp (ref "Q2")
      (value "MMBT3904")
      (footprint "eagle-import:SOT23-BEC")
      (libsource (lib "eagle-import") (part "-NPN-SOT23-BECMMBT3904LT1"))
    )
    (comp (ref "Q3")
      (value "MMBT3904")
      (footprint "eagle-import:SOT23-BEC")
      (libsource (lib "eagle-import") (part "-NPN-SOT23-BECMMBT3904LT1"))
    )
    (comp (ref "R22")
      (value "10k")
      (footprint "eagle-import:R0603")
      (libsource (lib "eagle-import") (part "R-US_R0603"))
    )
    (comp (ref "R23")
      (value "10k")
      (footprint "eagle-import:R0603")
      (libsource (lib "eagle-import") (part "R-US_R0603"))
    )
    (comp (ref "R24")
      (value "100k")
      (footprint "eagle-import:R0603")
      (libsource (lib "eagle-import") (part "R-US_R0603"))
    )
    (comp (ref "R25")
      (value "100k")
      (footprint "eagle-import:R0603")
      (libsource (lib "eagle-import") (part "R-US_R0603"))
    )
    (comp (ref "R26")
      (value "100k")
      (footprint "eagle-import:R0603")
      (libsource (lib "eagle-import") (part "R-US_R0603"))
    )
    (comp (ref "R27")
      (value "100k")
      (footprint "eagle-import:R0603")
      (libsource (lib "eagle-import") (part "R-US_R0603"))
    )
    (comp (ref "R28")
      (value "200k")
      (footprint "eagle-import:R0603")
      (libsource (lib "eagle-import") (part "R-US_R0603"))
    )
    (comp (ref "R29")
      (value "200k")
      (footprint "eagle-import:R0603")
      (libsource (lib "eagle-import") (part "R-US_R0603"))
    )
    (comp (ref "R30")
      (value "200k")
      (footprint "eagle-import:R0603")
      (libsource (lib "eagle-import") (part "R-US_R0603"))
    )
    (comp (ref "R31")
      (value "200k")
      (footprint "eagle-import:R0603")
      (libsource (lib "eagle-import") (part "R-US_R0603"))
    )
    (comp (ref "R32")
      (value "100k")
      (footprint "eagle-import:R0603")
      (libsource (lib "eagle-import") (part "R-US_R0603"))
    )
    (comp (ref "R33")
      (value "100k")
      (footprint "eagle-import:R0603")
      (libsource (lib "eagle-import") (part "R-US_R0603"))
    )
    (comp (ref "R34")
      (value "100k")
      (footprint "eagle-import:R0603")
      (libsource (lib "eagle-import") (part "R-US_R0603"))
    )
    (comp (ref "R35")
      (value "100k")
      (footprint "eagle-import:R0603")
      (libsource (lib "eagle-import") (part "R-US_R0603"))
    )
    (comp (ref "R39")
      (value "33k")
      (footprint "eagle-import:R0603")
      (libsource (lib "eagle-import") (part "R-US_R0603"))
    )
    (comp (ref "R40")
      (value "33k")
      (footprint "eagle-import:R0603")
      (libsource (lib "eagle-import") (part "R-US_R0603"))
    )
    (comp (ref "R41")
      (value "33k")
      (footprint "eagle-import:R0603")
      (libsource (lib "eagle-import") (part "R-US_R0603"))
    )
    (comp (ref "R42")
      (value "33k")
      (footprint "eagle-import:R0603")
      (libsource (lib "eagle-import") (part "R-US_R0603"))
    )
    (comp (ref "R57")
      (value "33k")
      (footprint "eagle-import:R0603")
      (libsource (lib "eagle-import") (part "R-US_R0603"))
    )
    (comp (ref "R58")
      (value "33k")
      (footprint "eagle-import:R0603")
      (libsource (lib "eagle-import") (part "R-US_R0603"))
    )
    (comp (ref "R59")
      (value "33k")
      (footprint "eagle-import:R0603")
      (libsource (lib "eagle-import") (part "R-US_R0603"))
    )
    (comp (ref "R64")
      (value "100k")
      (footprint "eagle-import:R0603")
      (libsource (lib "eagle-import") (part "R-US_R0603"))
    )
    (comp (ref "R65")
      (value "100k")
      (footprint "eagle-import:R0603")
      (libsource (lib "eagle-import") (part "R-US_R0603"))
    )
    (comp (ref "R66")
      (value "100k")
      (footprint "eagle-import:R0603")
      (libsource (lib "eagle-import") (part "R-US_R0603"))
    )
    (comp (ref "R70")
      (value "200k")
      (footprint "eagle-import:R0603")
      (libsource (lib "eagle-import") (part "R-US_R0603"))
    )
    (comp (ref "R71")
      (value "200k")
      (footprint "eagle-import:R0603")
      (libsource (lib "eagle-import") (part "R-US_R0603"))
    )
    (comp (ref "R72")
      (value "200k")
      (footprint "eagle-import:R0603")
      (libsource (lib "eagle-import") (part "R-US_R0603"))
    )
    (comp (ref "R76")
      (value "100k")
      (footprint "eagle-import:R0603")
      (libsource (lib "eagle-import") (part "R-US_R0603"))
    )
    (comp (ref "R77")
      (value "100k")
      (footprint "eagle-import:R0603")
      (libsource (lib "eagle-import") (part "R-US_R0603"))
    )
    (comp (ref "C8")
      (value "100n")
      (footprint "eagle-import:C0603")
      (libsource (lib "eagle-import") (part "C-USC0603"))
    )
    (comp (ref "C17")
      (value "100n")
      (footprint "eagle-import:C0603")
      (libsource (lib "eagle-import") (part "C-USC0603"))
    )
    (comp (ref "C18")
      (value "100n")
      (footprint "eagle-import:C0603")
      (libsource (lib "eagle-import") (part "C-USC0603"))
    )
    (comp (ref "C24")
      (value "100n")
      (footprint "eagle-import:C0603")
      (libsource (lib "eagle-import") (part "C-USC0603"))
    )
    (comp (ref "C28")
      (value "100n")
      (footprint "eagle-import:C0603")
      (libsource (lib "eagle-import") (part "C-USC0603"))
    )
    (comp (ref "C29")
      (value "100n")
      (footprint "eagle-import:C0603")
      (libsource (lib "eagle-import") (part "C-USC0603"))
    )
    (comp (ref "C36")
      (value "100n")
      (footprint "eagle-import:C0603")
      (libsource (lib "eagle-import") (part "C-USC0603"))
    )
    (comp (ref "C38")
      (value "100n")
      (footprint "eagle-import:C0603")
      (libsource (lib "eagle-import") (part "C-USC0603"))
    )
    (comp (ref "LED1")
      (value "W115WSURKMGKW")
      (footprint "eagle-import:LED-BICOLOR-THROUGHHOLE-2.54")
      (libsource (lib "eagle-import") (part "LED-BICOLOR-THROUGHHOLE2.54"))
    )
    (comp (ref "LED2")
      (value "W115WSURKMGKW")
      (footprint "eagle-import:LED-BICOLOR-THROUGHHOLE-2.54")
      (libsource (lib "eagle-import") (part "LED-BICOLOR-THROUGHHOLE2.54"))
    )
    (comp (ref "LED3")
      (value "W115WSURKMGKW")
      (footprint "eagle-import:LED-BICOLOR-THROUGHHOLE-2.54")
      (libsource (lib "eagle-import") (part "LED-BICOLOR-THROUGHHOLE2.54"))
    )
    (comp (ref "LED4")
      (value "W115WSURKMGKW")
      (footprint "eagle-import:LED-BICOLOR-THROUGHHOLE-2.54")
      (libsource (lib "eagle-import") (part "LED-BICOLOR-THROUGHHOLE2.54"))
    )
    (comp (ref "LED5")
      (value "W115WSURKMGKW")
      (footprint "eagle-import:LED-BICOLOR-THROUGHHOLE-2.54")
      (libsource (lib "eagle-import") (part "LED-BICOLOR-THROUGHHOLE2.54"))
    )
    (comp (ref "R1")
      (value "39")
      (footprint "eagle-import:R0603")
      (libsource (lib "eagle-import") (part "R-US_R0603"))
    )
    (comp (ref "R4")
      (value "10kB")
      (footprint "eagle-import:ALPS_POT_VERTICAL_PS")
      (libsource (lib "eagle-import") (part "POT_USVERTICAL_PS"))
    )
    (comp (ref "R5")
      (value "39")
      (footprint "eagle-import:R0603")
      (libsource (lib "eagle-import") (part "R-US_R0603"))
    )
    (comp (ref "R9")
      (value "2.2k")
      (footprint "eagle-import:R0603")
      (libsource (lib "eagle-import") (part "R-US_R0603"))
    )
    (comp (ref "R10")
      (value "1.5k")
      (footprint "eagle-import:R0603")
      (libsource (lib "eagle-import") (part "R-US_R0603"))
    )
    (comp (ref "R11")
      (value "2.2k")
      (footprint "eagle-import:R0603")
      (libsource (lib "eagle-import") (part "R-US_R0603"))
    )
    (comp (ref "R12")
      (value "1.5k")
      (footprint "eagle-import:R0603")
      (libsource (lib "eagle-import") (part "R-US_R0603"))
    )
    (comp (ref "R13")
      (value "10kB")
      (footprint "eagle-import:ALPS_POT_VERTICAL_PS")
      (libsource (lib "eagle-import") (part "POT_USVERTICAL_PS"))
    )
    (comp (ref "R14")
      (value "10kB")
      (footprint "eagle-import:ALPS_POT_VERTICAL_PS")
      (libsource (lib "eagle-import") (part "POT_USVERTICAL_PS"))
    )
    (comp (ref "R15")
      (value "2.2k")
      (footprint "eagle-import:R0603")
      (libsource (lib "eagle-import") (part "R-US_R0603"))
    )
    (comp (ref "R16")
      (value "10kB")
      (footprint "eagle-import:ALPS_POT_VERTICAL_PS")
      (libsource (lib "eagle-import") (part "POT_USVERTICAL_PS"))
    )
    (comp (ref "R17")
      (value "1.5k")
      (footprint "eagle-import:R0603")
      (libsource (lib "eagle-import") (part "R-US_R0603"))
    )
    (comp (ref "R18")
      (value "1.5k")
      (footprint "eagle-import:R0603")
      (libsource (lib "eagle-import") (part "R-US_R0603"))
    )
    (comp (ref "R19")
      (value "2.2k")
      (footprint "eagle-import:R0603")
      (libsource (lib "eagle-import") (part "R-US_R0603"))
    )
    (comp (ref "R20")
      (value "10kB")
      (footprint "eagle-import:ALPS_POT_VERTICAL_PS")
      (libsource (lib "eagle-import") (part "POT_USVERTICAL_PS"))
    )
    (comp (ref "R21")
      (value "10kB")
      (footprint "eagle-import:ALPS_POT_VERTICAL_PS")
      (libsource (lib "eagle-import") (part "POT_USVERTICAL_PS"))
    )
    (comp (ref "R36")
      (value "1.5k")
      (footprint "eagle-import:R0603")
      (libsource (lib "eagle-import") (part "R-US_R0603"))
    )
    (comp (ref "R37")
      (value "10kB")
      (footprint "eagle-import:ALPS_POT_VERTICAL_PS")
      (libsource (lib "eagle-import") (part "POT_USVERTICAL_PS"))
    )
    (comp (ref "R38")
      (value "10kB")
      (footprint "eagle-import:ALPS_POT_VERTICAL_PS")
      (libsource (lib "eagle-import") (part "POT_USVERTICAL_PS"))
    )
    (comp (ref "SW1")
      (value "LP4OA1PBCT")
      (footprint "eagle-import:LP4OA1PBCT")
      (libsource (lib "eagle-import") (part "LP4OA1PBCT"))
    )
    (comp (ref "SW2")
      (value "LP4OA1PBCT")
      (footprint "eagle-import:LP4OA1PBCT")
      (libsource (lib "eagle-import") (part "LP4OA1PBCT"))
    )
    (comp (ref "SW3")
      (value "TAC_SWITCHPTH")
      (footprint "eagle-import:TACTILE-PTH")
      (libsource (lib "eagle-import") (part "TAC_SWITCHPTH"))
    )
    (comp (ref "SW4")
      (value "TAC_SWITCHPTH")
      (footprint "eagle-import:TACTILE-PTH")
      (libsource (lib "eagle-import") (part "TAC_SWITCHPTH"))
    )
    (comp (ref "SW5")
      (value "TAC_SWITCHPTH")
      (footprint "eagle-import:TACTILE-PTH")
      (libsource (lib "eagle-import") (part "TAC_SWITCHPTH"))
    )
    (comp (ref "SW6")
      (value "TAC_SWITCHPTH")
      (footprint "eagle-import:TACTILE-PTH")
      (libsource (lib "eagle-import") (part "TAC_SWITCHPTH"))
    )
    (comp (ref "SW7")
      (value "TAC_SWITCHPTH")
      (footprint "eagle-import:TACTILE-PTH")
      (libsource (lib "eagle-import") (part "TAC_SWITCHPTH"))
    )
  )
  (nets
    (net (code "1") (name "+3V3") (class "Default")
      (node (ref "C1") (pin "1") (pinfunction "1_1") (pintype "passive"))
      (node (ref "C12") (pin "1") (pinfunction "1_1") (pintype "passive"))
      (node (ref "C13") (pin "1") (pinfunction "1_1") (pintype "passive"))
      (node (ref "C16") (pin "1") (pinfunction "1_1") (pintype "passive"))
      (node (ref "C19") (pin "1") (pinfunction "1_1") (pintype "passive"))
      (node (ref "C2") (pin "+") (pinfunction "+_+") (pintype "passive"))
      (node (ref "C21") (pin "1") (pinfunction "1_1") (pintype "passive"))
      (node (ref "D3") (pin "2") (pinfunction "C_2") (pintype "passive"))
      (node (ref "IC1") (pin "3") (pinfunction "VO_3") (pintype "passive"))
      (node (ref "IC2") (pin "1") (pinfunction "VBAT_1") (pintype "power_in"))
      (node (ref "IC2") (pin "19") (pinfunction "VDD_4_19") (pintype "power_in"))
      (node (ref "IC2") (pin "32") (pinfunction "VDD_1_32") (pintype "power_in"))
      (node (ref "IC2") (pin "48") (pinfunction "VDD_2_48") (pintype "power_in"))
      (node (ref "IC2") (pin "64") (pinfunction "VDD_3_64") (pintype "power_in"))
      (node (ref "IC4") (pin "12") (pinfunction "DVDD_12") (pintype "power_in"))
      (node (ref "R22") (pin "2") (pinfunction "2_2") (pintype "passive"))
      (node (ref "R23") (pin "2") (pinfunction "2_2") (pintype "passive"))
      (node (ref "R6") (pin "2") (pinfunction "2_2") (pintype "passive"))
    )
    (net (code "2") (name "+3V3_A") (class "Default")
      (node (ref "C10") (pin "1") (pinfunction "1_1") (pintype "passive"))
      (node (ref "C23") (pin "+") (pinfunction "+_+") (pintype "passive"))
      (node (ref "C26") (pin "1") (pinfunction "1_1") (pintype "passive"))
      (node (ref "C27") (pin "+") (pinfunction "+_+") (pintype "passive"))
      (node (ref "C46") (pin "1") (pinfunction "1_1") (pintype "passive"))
      (node (ref "C47") (pin "1") (pinfunction "1_1") (pintype "passive"))
      (node (ref "C9") (pin "1") (pinfunction "1_1") (pintype "passive"))
      (node (ref "IC2") (pin "13") (pinfunction "VDDA_13") (pintype "power_in"))
      (node (ref "IC3") (pin "1") (pinfunction "VO_1") (pintype "passive"))
      (node (ref "IC4") (pin "4") (pinfunction "AVDD_4") (pintype "power_in"))
      (node (ref "IC5") (pin "4") (pinfunction "V+_4") (pintype "power_in"))
      (node (ref "IC6") (pin "4") (pinfunction "V+_4") (pintype "power_in"))
      (node (ref "R13") (pin "P$1") (pinfunction "E_P$1") (pintype "passive"))
      (node (ref "R14") (pin "P$1") (pinfunction "E_P$1") (pintype "passive"))
      (node (ref "R16") (pin "P$1") (pinfunction "E_P$1") (pintype "passive"))
      (node (ref "R20") (pin "P$1") (pinfunction "E_P$1") (pintype "passive"))
      (node (ref "R21") (pin "P$1") (pinfunction "E_P$1") (pintype "passive"))
      (node (ref "R37") (pin "P$1") (pinfunction "E_P$1") (pintype "passive"))
      (node (ref "R38") (pin "P$1") (pinfunction "E_P$1") (pintype "passive"))
      (node (ref "R4") (pin "P$1") (pinfunction "E_P$1") (pintype "passive"))
    )
    (net (code "3") (name "ADC_DV_CV") (class "Default")
      (node (ref "C33") (pin "2") (pinfunction "2_2") (pintype "passive"))
      (node (ref "IC2") (pin "21") (pinfunction "PA5/SPI1_SCK/ADC5/DAC2_21") (pintype "bidirectional"))
      (node (ref "IC6") (pin "8") (pinfunction "OUT_8") (pintype "output"))
      (node (ref "R42") (pin "1") (pinfunction "1_1") (pintype "passive"))
    )
    (net (code "4") (name "ADC_DV_POT") (class "Default")
      (node (ref "C8") (pin "1") (pinfunction "1_1") (pintype "passive"))
      (node (ref "IC2") (pin "11") (pinfunction "PC3/SPI2_MOSI/I2S2_SD/ADC13_11") (pintype "bidirectional"))
      (node (ref "R4") (pin "P$2") (pinfunction "S_P$2") (pintype "passive"))
    )
    (net (code "5") (name "ADC_LENGTH_POT") (class "Default")
      (node (ref "C24") (pin "1") (pinfunction "1_1") (pintype "passive"))
      (node (ref "IC2") (pin "27") (pinfunction "PB1/ADC9/TIM3_CH4_27") (pintype "bidirectional"))
      (node (ref "R16") (pin "P$2") (pinfunction "S_P$2") (pintype "passive"))
    )
    (net (code "6") (name "ADC_T_BIAS_CV") (class "Default")
      (node (ref "C40") (pin "2") (pinfunction "2_2") (pintype "passive"))
      (node (ref "IC2") (pin "15") (pinfunction "PA1/USART2_RTS/UART4_RX/ADC1/TIM2_CH2_15") (pintype "bidirectional"))
      (node (ref "IC5") (pin "1") (pinfunction "OUT_1") (pintype "output"))
      (node (ref "R57") (pin "1") (pinfunction "1_1") (pintype "passive"))
    )
    (net (code "7") (name "ADC_T_BIAS_POT") (class "Default")
      (node (ref "C28") (pin "1") (pinfunction "1_1") (pintype "passive"))
      (node (ref "IC2") (pin "16") (pinfunction "PA2/USART2_TX/ADC2/TIM2_CH3_16") (pintype "bidirectional"))
      (node (ref "R20") (pin "P$2") (pinfunction "S_P$2") (pintype "passive"))
    )
    (net (code "8") (name "ADC_T_JITTER_CV") (class "Default")
      (node (ref "C42") (pin "2") (pinfunction "2_2") (pintype "passive"))
      (node (ref "IC2") (pin "20") (pinfunction "PA4/SPI1_NSS/SPI3_NSS/USART2_CK/I2S3_WS/ADC4/DAC1_20") (pintype "bidirectional"))
      (node (ref "IC6") (pin "7") (pinfunction "OUT_7") (pintype "output"))
      (node (ref "R59") (pin "1") (pinfunction "1_1") (pintype "passive"))
    )
    (net (code "9") (name "ADC_T_JITTER_POT") (class "Default")
      (node (ref "C38") (pin "1") (pinfunction "1_1") (pintype "passive"))
      (node (ref "IC2") (pin "25") (pinfunction "PC5/ADC15_25") (pintype "bidirectional"))
      (node (ref "R37") (pin "P$2") (pinfunction "S_P$2") (pintype "passive"))
    )
    (net (code "10") (name "ADC_T_RATE_CV") (class "Default")
      (node (ref "C41") (pin "2") (pinfunction "2_2") (pintype "passive"))
      (node (ref "IC2") (pin "17") (pinfunction "PA3/USART2_RX/ADC3/TIM2_CH4_17") (pintype "bidirectional"))
      (node (ref "IC6") (pin "1") (pinfunction "OUT_1") (pintype "output"))
      (node (ref "R58") (pin "1") (pinfunction "1_1") (pintype "passive"))
    )
    (net (code "11") (name "ADC_T_RATE_POT") (class "Default")
      (node (ref "C17") (pin "1") (pinfunction "1_1") (pintype "passive"))
      (node (ref "IC2") (pin "10") (pinfunction "PC2/SPI2_MISO/ADC12_10") (pintype "bidirectional"))
      (node (ref "R13") (pin "P$2") (pinfunction "S_P$2") (pintype "passive"))
    )
    (net (code "12") (name "ADC_X_BIAS_CV") (class "Default")
      (node (ref "C30") (pin "2") (pinfunction "2_2") (pintype "passive"))
      (node (ref "IC2") (pin "24") (pinfunction "PC4/ADC14_24") (pintype "bidirectional"))
      (node (ref "IC5") (pin "14") (pinfunction "OUT_14") (pintype "output"))
      (node (ref "R39") (pin "1") (pinfunction "1_1") (pintype "passive"))
    )
    (net (code "13") (name "ADC_X_BIAS_POT") (class "Default")
      (node (ref "C29") (pin "1") (pinfunction "1_1") (pintype "passive"))
      (node (ref "IC2") (pin "9") (pinfunction "PC1/ADC11_9") (pintype "bidirectional"))
      (node (ref "R21") (pin "P$2") (pinfunction "S_P$2") (pintype "passive"))
    )
    (net (code "14") (name "ADC_X_SPREAD_CV") (class "Default")
      (node (ref "C31") (pin "2") (pinfunction "2_2") (pintype "passive"))
      (node (ref "IC2") (pin "14") (pinfunction "PA0-WKUP/USART2_CTS/UART4_TX/ADC0/TIM2_CH1_ETR_14") (pintype "bidirectional"))
      (node (ref "IC2") (pin "23") (pinfunction "PA7/SPI1_MOSI/ADC7/TIM3_CH2_23") (pintype "bidirectional"))
      (node (ref "IC5") (pin "8") (pinfunction "OUT_8") (pintype "output"))
      (node (ref "R40") (pin "1") (pinfunction "1_1") (pintype "passive"))
    )
    (net (code "15") (name "ADC_X_SPREAD_POT") (class "Default")
      (node (ref "C18") (pin "1") (pinfunction "1_1") (pintype "passive"))
      (node (ref "IC2") (pin "8") (pinfunction "PC0/ADC10_8") (pintype "bidirectional"))
      (node (ref "R14") (pin "P$2") (pinfunction "S_P$2") (pintype "passive"))
    )
    (net (code "16") (name "ADC_X_STEPS_CV") (class "Default")
      (node (ref "C32") (pin "2") (pinfunction "2_2") (pintype "passive"))
      (node (ref "IC2") (pin "22") (pinfunction "PA6/SPI1_MISO/ADC6/TIM3_CH1_22") (pintype "bidirectional"))
      (node (ref "IC6") (pin "14") (pinfunction "OUT_14") (pintype "output"))
      (node (ref "R41") (pin "1") (pinfunction "1_1") (pintype "passive"))
    )
    (net (code "17") (name "ADC_X_STEPS_POT") (class "Default")
      (node (ref "C36") (pin "1") (pinfunction "1_1") (pintype "passive"))
      (node (ref "IC2") (pin "26") (pinfunction "PB0/ADC8/TIM3_CH3_26") (pintype "bidirectional"))
      (node (ref "R38") (pin "P$2") (pinfunction "S_P$2") (pintype "passive"))
    )
    (net (code "18") (name "AREF_-10") (class "Default")
      (node (ref "C52") (pin "1") (pinfunction "1_1") (pintype "passive"))
      (node (ref "IC8") (pin "2") (pinfunction "A_2") (pintype "passive"))
      (node (ref "R28") (pin "2") (pinfunction "2_2") (pintype "passive"))
      (node (ref "R29") (pin "2") (pinfunction "2_2") (pintype "passive"))
      (node (ref "R30") (pin "2") (pinfunction "2_2") (pintype "passive"))
      (node (ref "R31") (pin "2") (pinfunction "2_2") (pintype "passive"))
      (node (ref "R68") (pin "2") (pinfunction "2_2") (pintype "passive"))
      (node (ref "R70") (pin "2") (pinfunction "2_2") (pintype "passive"))
      (node (ref "R71") (pin "2") (pinfunction "2_2") (pintype "passive"))
      (node (ref "R72") (pin "2") (pinfunction "2_2") (pintype "passive"))
    )
    (net (code "19") (name "DAC_MOSI") (class "Default")
      (node (ref "IC2") (pin "53") (pinfunction "PC12/UART5_TX/I2S3_SD/USART3_CK_53") (pintype "bidirectional"))
      (node (ref "IC4") (pin "11") (pinfunction "IN_11") (pintype "input"))
    )
    (net (code "20") (name "DAC_SCK") (class "Default")
      (node (ref "IC2") (pin "51") (pinfunction "PC10/SPI3_SCK/I2S3_SCK/UART4_TX_51") (pintype "bidirectional"))
      (node (ref "IC4") (pin "10") (pinfunction "SCK_10") (pintype "input"))
    )
    (net (code "21") (name "DAC_SS") (class "Default")
      (node (ref "IC2") (pin "50") (pinfunction "PA15/JTDI/SPI3_NSS/I2S3_WS_50") (pintype "bidirectional"))
      (node (ref "IC4") (pin "9") (pinfunction "SYNC_9") (pintype "input"))
    )
    (net (code "22") (name "DAC_X_1") (class "Default")
      (node (ref "IC4") (pin "2") (pinfunction "OUTB_2") (pintype "output"))
      (node (ref "R47") (pin "2") (pinfunction "2_2") (pintype "passive"))
    )
    (net (code "23") (name "DAC_X_2") (class "Default")
      (node (ref "IC4") (pin "7") (pinfunction "OUTC_7") (pintype "output"))
      (node (ref "R48") (pin "2") (pinfunction "2_2") (pintype "passive"))
    )
    (net (code "24") (name "DAC_X_3") (class "Default")
      (node (ref "IC4") (pin "8") (pinfunction "OUTD_8") (pintype "output"))
      (node (ref "R53") (pin "2") (pinfunction "2_2") (pintype "passive"))
    )
    (net (code "25") (name "DAC_Y") (class "Default")
      (node (ref "IC4") (pin "1") (pinfunction "OUTA_1") (pintype "output"))
      (node (ref "R54") (pin "2") (pinfunction "2_2") (pintype "passive"))
    )
    (net (code "26") (name "DEPRECATED") (class "Default")
      (node (ref "IC5") (pin "6") (pinfunction "-IN_6") (pintype "input"))
      (node (ref "IC5") (pin "7") (pinfunction "OUT_7") (pintype "output"))
    )
    (net (code "27") (name "GATE_T_1") (class "Default")
      (node (ref "IC2") (pin "52") (pinfunction "PC11/UART4_RX/SPI3_MISO/USART3_RX_52") (pintype "bidirectional"))
      (node (ref "LED6") (pin "1") (pinfunction "1_1") (pintype "bidirectional"))
      (node (ref "R56") (pin "2") (pinfunction "2_2") (pintype "passive"))
    )
    (net (code "28") (name "GATE_T_2") (class "Default")
      (node (ref "IC2") (pin "44") (pinfunction "PA11/USART1_CTS/CANRX/USBDM/TIM1_CH4_44") (pintype "bidirectional"))
      (node (ref "LED7") (pin "1") (pinfunction "1_1") (pintype "bidirectional"))
      (node (ref "R55") (pin "2") (pinfunction "2_2") (pintype "passive"))
    )
    (net (code "29") (name "GATE_T_3") (class "Default")
      (node (ref "IC2") (pin "45") (pinfunction "PA12/USART1_RTS/CANTX/USBDP/TIM1_ETR_45") (pintype "bidirectional"))
      (node (ref "LED8") (pin "1") (pinfunction "1_1") (pintype "bidirectional"))
      (node (ref "R67") (pin "2") (pinfunction "2_2") (pintype "passive"))
    )
    (net (code "30") (name "GND") (class "Default")
      (node (ref "C1") (pin "2") (pinfunction "2_2") (pintype "passive"))
      (node (ref "C10") (pin "2") (pinfunction "2_2") (pintype "passive"))
      (node (ref "C11") (pin "-") (pinfunction "-_-") (pintype "passive"))
      (node (ref "C12") (pin "2") (pinfunction "2_2") (pintype "passive"))
      (node (ref "C13") (pin "2") (pinfunction "2_2") (pintype "passive"))
      (node (ref "C14") (pin "2") (pinfunction "2_2") (pintype "passive"))
      (node (ref "C15") (pin "2") (pinfunction "2_2") (pintype "passive"))
      (node (ref "C16") (pin "2") (pinfunction "2_2") (pintype "passive"))
      (node (ref "C17") (pin "2") (pinfunction "2_2") (pintype "passive"))
      (node (ref "C18") (pin "2") (pinfunction "2_2") (pintype "passive"))
      (node (ref "C19") (pin "2") (pinfunction "2_2") (pintype "passive"))
      (node (ref "C2") (pin "-") (pinfunction "-_-") (pintype "passive"))
      (node (ref "C20") (pin "2") (pinfunction "2_2") (pintype "passive"))
      (node (ref "C21") (pin "2") (pinfunction "2_2") (pintype "passive"))
      (node (ref "C22") (pin "+") (pinfunction "+_+") (pintype "passive"))
      (node (ref "C23") (pin "-") (pinfunction "-_-") (pintype "passive"))
      (node (ref "C24") (pin "2") (pinfunction "2_2") (pintype "passive"))
      (node (ref "C25") (pin "2") (pinfunction "2_2") (pintype "passive"))
      (node (ref "C26") (pin "2") (pinfunction "2_2") (pintype "passive"))
      (node (ref "C27") (pin "-") (pinfunction "-_-") (pintype "passive"))
      (node (ref "C28") (pin "2") (pinfunction "2_2") (pintype "passive"))
      (node (ref "C29") (pin "2") (pinfunction "2_2") (pintype "passive"))
      (node (ref "C3") (pin "2") (pinfunction "2_2") (pintype "passive"))
      (node (ref "C36") (pin "2") (pinfunction "2_2") (pintype "passive"))
      (node (ref "C37") (pin "1") (pinfunction "1_1") (pintype "passive"))
      (node (ref "C38") (pin "2") (pinfunction "2_2") (pintype "passive"))
      (node (ref "C39") (pin "2") (pinfunction "2_2") (pintype "passive"))
      (node (ref "C4") (pin "1") (pinfunction "1_1") (pintype "passive"))
      (node (ref "C45") (pin "2") (pinfunction "2_2") (pintype "passive"))
      (node (ref "C46") (pin "2") (pinfunction "2_2") (pintype "passive"))
      (node (ref "C47") (pin "2") (pinfunction "2_2") (pintype "passive"))
      (node (ref "C48") (pin "2") (pinfunction "2_2") (pintype "passive"))
      (node (ref "C49") (pin "1") (pinfunction "1_1") (pintype "passive"))
      (node (ref "C5") (pin "2") (pinfunction "2_2") (pintype "passive"))
      (node (ref "C50") (pin "2") (pinfunction "2_2") (pintype "passive"))
      (node (ref "C51") (pin "2") (pinfunction "2_2") (pintype "passive"))
      (node (ref "C52") (pin "2") (pinfunction "2_2") (pintype "passive"))
      (node (ref "C53") (pin "2") (pinfunction "2_2") (pintype "passive"))
      (node (ref "C54") (pin "2") (pinfunction "2_2") (pintype "passive"))
      (node (ref "C55") (pin "2") (pinfunction "2_2") (pintype "passive"))
      (node (ref "C56") (pin "2") (pinfunction "2_2") (pintype "passive"))
      (node (ref "C57") (pin "2") (pinfunction "2_2") (pintype "passive"))
      (node (ref "C58") (pin "2") (pinfunction "2_2") (pintype "passive"))
      (node (ref "C6") (pin "1") (pinfunction "1_1") (pintype "passive"))
      (node (ref "C7") (pin "2") (pinfunction "2_2") (pintype "passive"))
      (node (ref "C8") (pin "2") (pinfunction "2_2") (pintype "passive"))
      (node (ref "C9") (pin "2") (pinfunction "2_2") (pintype "passive"))
      (node (ref "D3") (pin "1") (pinfunction "A_1") (pintype "passive"))
      (node (ref "D4") (pin "A") (pinfunction "A_A") (pintype "passive"))
      (node (ref "D5") (pin "A") (pinfunction "A_A") (pintype "passive"))
      (node (ref "IC1") (pin "2") (pinfunction "GND_2") (pintype "passive"))
      (node (ref "IC2") (pin "12") (pinfunction "VSSA_12") (pintype "power_in"))
      (node (ref "IC2") (pin "18") (pinfunction "VSS_4_18") (pintype "power_in"))
      (node (ref "IC2") (pin "28") (pinfunction "PB2/BOOT1_28") (pintype "bidirectional"))
      (node (ref "IC2") (pin "60") (pinfunction "BOOT0_60") (pintype "bidirectional"))
      (node (ref "IC2") (pin "63") (pinfunction "VSS_3_63") (pintype "power_in"))
      (node (ref "IC3") (pin "2") (pinfunction "GND_2") (pintype "passive"))
      (node (ref "IC4") (pin "13") (pinfunction "A0_13") (pintype "input"))
      (node (ref "IC4") (pin "14") (pinfunction "A1_14") (pintype "input"))
      (node (ref "IC4") (pin "15") (pinfunction "ENABLE_15") (pintype "input"))
      (node (ref "IC4") (pin "16") (pinfunction "LDAC_16") (pintype "input"))
      (node (ref "IC4") (pin "5") (pinfunction "VREFL_5") (pintype "bidirectional"))
      (node (ref "IC4") (pin "6") (pinfunction "GND_6") (pintype "power_in"))
      (node (ref "IC5") (pin "10") (pinfunction "+IN_10") (pintype "input"))
      (node (ref "IC5") (pin "11") (pinfunction "V-_11") (pintype "power_in"))
      (node (ref "IC5") (pin "12") (pinfunction "+IN_12") (pintype "input"))
      (node (ref "IC5") (pin "3") (pinfunction "+IN_3") (pintype "input"))
      (node (ref "IC5") (pin "5") (pinfunction "+IN_5") (pintype "input"))
      (node (ref "IC6") (pin "10") (pinfunction "+IN_10") (pintype "input"))
      (node (ref "IC6") (pin "11") (pinfunction "V-_11") (pintype "power_in"))
      (node (ref "IC6") (pin "12") (pinfunction "+IN_12") (pintype "input"))
      (node (ref "IC6") (pin "3") (pinfunction "+IN_3") (pintype "input"))
      (node (ref "IC6") (pin "5") (pinfunction "+IN_5") (pintype "input"))
      (node (ref "IC8") (pin "1") (pinfunction "C_1") (pintype "passive"))
      (node (ref "IC9") (pin "11") (pinfunction "V-_11") (pintype "power_in"))
      (node (ref "IC9") (pin "5") (pinfunction "+IN_5") (pintype "input"))
      (node (ref "J1") (pin "P1") (pinfunction "1_P1") (pintype "passive"))
      (node (ref "J1") (pin "P2") (pinfunction "2_P2") (pintype "passive"))
      (node (ref "J10") (pin "P1") (pinfunction "1_P1") (pintype "passive"))
      (node (ref "J11") (pin "P1") (pinfunction "1_P1") (pintype "passive"))
      (node (ref "J12") (pin "P1") (pinfunction "1_P1") (pintype "passive"))
      (node (ref "J13") (pin "P1") (pinfunction "1_P1") (pintype "passive"))
      (node (ref "J14") (pin "P1") (pinfunction "1_P1") (pintype "passive"))
      (node (ref "J15") (pin "P1") (pinfunction "1_P1") (pintype "passive"))
      (node (ref "J16") (pin "P1") (pinfunction "1_P1") (pintype "passive"))
      (node (ref "J2") (pin "P1") (pinfunction "1_P1") (pintype "passive"))
      (node (ref "J2") (pin "P2") (pinfunction "2_P2") (pintype "passive"))
      (node (ref "J3") (pin "P1") (pinfunction "1_P1") (pintype "passive"))
      (node (ref "J4") (pin "P1") (pinfunction "1_P1") (pintype "passive"))
      (node (ref "J4") (pin "P2") (pinfunction "2_P2") (pintype "passive"))
      (node (ref "J5") (pin "P1") (pinfunction "1_P1") (pintype "passive"))
      (node (ref "J5") (pin "P2") (pinfunction "2_P2") (pintype "passive"))
      (node (ref "J6") (pin "P1") (pinfunction "1_P1") (pintype "passive"))
      (node (ref "J6") (pin "P2") (pinfunction "2_P2") (pintype "passive"))
      (node (ref "J7") (pin "P1") (pinfunction "1_P1") (pintype "passive"))
      (node (ref "J7") (pin "P2") (pinfunction "2_P2") (pintype "passive"))
      (node (ref "J8") (pin "P1") (pinfunction "1_P1") (pintype "passive"))
      (node (ref "J8") (pin "P2") (pinfunction "2_P2") (pintype "passive"))
      (node (ref "J9") (pin "P1") (pinfunction "1_P1") (pintype "passive"))
      (node (ref "JP1") (pin "1") (pinfunction "1_1") (pintype "passive"))
      (node (ref "JP4") (pin "3") (pinfunction "3_3") (pintype "passive"))
      (node (ref "JP4") (pin "4") (pinfunction "4_4") (pintype "passive"))
      (node (ref "JP4") (pin "5") (pinfunction "5_5") (pintype "passive"))
      (node (ref "JP4") (pin "6") (pinfunction "6_6") (pintype "passive"))
      (node (ref "JP4") (pin "7") (pinfunction "7_7") (pintype "passive"))
      (node (ref "JP4") (pin "8") (pinfunction "8_8") (pintype "passive"))
      (node (ref "LED1") (pin "2") (pinfunction "C_2") (pintype "bidirectional"))
      (node (ref "LED2") (pin "2") (pinfunction "C_2") (pintype "bidirectional"))
      (node (ref "LED3") (pin "2") (pinfunction "C_2") (pintype "bidirectional"))
      (node (ref "LED4") (pin "2") (pinfunction "C_2") (pintype "bidirectional"))
      (node (ref "LED5") (pin "2") (pinfunction "C_2") (pintype "bidirectional"))
      (node (ref "Q1") (pin "2") (pinfunction "LID1_2") (pintype "power_in"))
      (node (ref "Q1") (pin "4") (pinfunction "LID2_4") (pintype "power_in"))
      (node (ref "Q2") (pin "E") (pinfunction "E_E") (pintype "passive"))
      (node (ref "Q3") (pin "E") (pinfunction "E_E") (pintype "passive"))
      (node (ref "R13") (pin "P$3") (pinfunction "A_P$3") (pintype "passive"))
      (node (ref "R14") (pin "P$3") (pinfunction "A_P$3") (pintype "passive"))
      (node (ref "R16") (pin "P$3") (pinfunction "A_P$3") (pintype "passive"))
      (node (ref "R20") (pin "P$3") (pinfunction "A_P$3") (pintype "passive"))
      (node (ref "R21") (pin "P$3") (pinfunction "A_P$3") (pintype "passive"))
      (node (ref "R24") (pin "1") (pinfunction "1_1") (pintype "passive"))
      (node (ref "R25") (pin "1") (pinfunction "1_1") (pintype "passive"))
      (node (ref "R37") (pin "P$3") (pinfunction "A_P$3") (pintype "passive"))
      (node (ref "R38") (pin "P$3") (pinfunction "A_P$3") (pintype "passive"))
      (node (ref "R4") (pin "P$3") (pinfunction "A_P$3") (pintype "passive"))
      (node (ref "R49") (pin "2") (pinfunction "2_2") (pintype "passive"))
      (node (ref "R50") (pin "2") (pinfunction "2_2") (pintype "passive"))
      (node (ref "R73") (pin "1") (pinfunction "1_1") (pintype "passive"))
      (node (ref "R75") (pin "2") (pinfunction "2_2") (pintype "passive"))
      (node (ref "R78") (pin "2") (pinfunction "2_2") (pintype "passive"))
      (node (ref "R79") (pin "2") (pinfunction "2_2") (pintype "passive"))
      (node (ref "R80") (pin "2") (pinfunction "2_2") (pintype "passive"))
      (node (ref "R81") (pin "2") (pinfunction "2_2") (pintype "passive"))
      (node (ref "R82") (pin "1") (pinfunction "1_1") (pintype "passive"))
      (node (ref "R83") (pin "1") (pinfunction "1_1") (pintype "passive"))
      (node (ref "R84") (pin "1") (pinfunction "1_1") (pintype "passive"))
      (node (ref "SW1") (pin "L2") (pinfunction "L2_L2") (pintype "passive"))
      (node (ref "SW1") (pin "P3") (pinfunction "A3_P3") (pintype "passive"))
      (node (ref "SW1") (pin "P6") (pinfunction "B3_P6") (pintype "passive"))
      (node (ref "SW2") (pin "L2") (pinfunction "L2_L2") (pintype "passive"))
      (node (ref "SW2") (pin "P3") (pinfunction "A3_P3") (pintype "passive"))
      (node (ref "SW2") (pin "P6") (pinfunction "B3_P6") (pintype "passive"))
      (node (ref "SW3") (pin "1") (pinfunction "1_1") (pintype "passive"))
      (node (ref "SW3") (pin "2") (pinfunction "2_2") (pintype "passive"))
      (node (ref "SW4") (pin "1") (pinfunction "1_1") (pintype "passive"))
      (node (ref "SW4") (pin "2") (pinfunction "2_2") (pintype "passive"))
      (node (ref "SW5") (pin "1") (pinfunction "1_1") (pintype "passive"))
      (node (ref "SW5") (pin "2") (pinfunction "2_2") (pintype "passive"))
      (node (ref "SW6") (pin "1") (pinfunction "1_1") (pintype "passive"))
      (node (ref "SW6") (pin "2") (pinfunction "2_2") (pintype "passive"))
      (node (ref "SW7") (pin "1") (pinfunction "1_1") (pintype "passive"))
      (node (ref "SW7") (pin "2") (pinfunction "2_2") (pintype "passive"))
    )
    (net (code "31") (name "LED_T_DV") (class "Default")
      (node (ref "IC2") (pin "29") (pinfunction "PB10/SPI2_SCK/I2S_SCK/I2C2_SCL/USART3_TX_29") (pintype "bidirectional"))
      (node (ref "R1") (pin "1") (pinfunction "1_1") (pintype "passive"))
    )
    (net (code "32") (name "LED_T_MODE_G") (class "Default")
      (node (ref "IC2") (pin "33") (pinfunction "PB12/SPI2_NSS/I2S2_WS/I2C2_SMBA/USART3_CK/TIM1_BKIN_33") (pintype "bidirectional"))
      (node (ref "R10") (pin "1") (pinfunction "1_1") (pintype "passive"))
    )
    (net (code "33") (name "LED_T_MODE_R") (class "Default")
      (node (ref "IC2") (pin "34") (pinfunction "PB13/SPI2_SCK/I2S2_SCK/USART3_CTS/TIM1_CH1N_34") (pintype "bidirectional"))
      (node (ref "R9") (pin "1") (pinfunction "1_1") (pintype "passive"))
    )
    (net (code "34") (name "LED_T_RANGE_G") (class "Default")
      (node (ref "IC2") (pin "37") (pinfunction "PC6/I2S2_MCK_37") (pintype "bidirectional"))
      (node (ref "R18") (pin "1") (pinfunction "1_1") (pintype "passive"))
    )
    (net (code "35") (name "LED_T_RANGE_R") (class "Default")
      (node (ref "IC2") (pin "38") (pinfunction "PC7/I2S3_MCK_38") (pintype "bidirectional"))
      (node (ref "R19") (pin "1") (pinfunction "1_1") (pintype "passive"))
    )
    (net (code "36") (name "LED_X_DV") (class "Default")
      (node (ref "IC2") (pin "62") (pinfunction "PB9/SPI2_NSS/I2S2_WS/I2C1_SDA/TIM4_CH4_62") (pintype "bidirectional"))
      (node (ref "R5") (pin "1") (pinfunction "1_1") (pintype "passive"))
    )
    (net (code "37") (name "LED_X_EXT_G") (class "Default")
      (node (ref "IC2") (pin "55") (pinfunction "PB3/JTDO/SPI3_SCK/I2S3_SCK_55") (pintype "bidirectional"))
      (node (ref "R36") (pin "1") (pinfunction "1_1") (pintype "passive"))
    )
    (net (code "38") (name "LED_X_MODE_G") (class "Default")
      (node (ref "IC2") (pin "59") (pinfunction "PB7/I2C1_SDA/TIM4_CH2/USART1_RX_59") (pintype "bidirectional"))
      (node (ref "R12") (pin "1") (pinfunction "1_1") (pintype "passive"))
    )
    (net (code "39") (name "LED_X_MODE_R") (class "Default")
      (node (ref "IC2") (pin "61") (pinfunction "PB8/TIM4_CH3/I2C1_SCL_61") (pintype "bidirectional"))
      (node (ref "R11") (pin "1") (pinfunction "1_1") (pintype "passive"))
    )
    (net (code "40") (name "LED_X_RANGE_G") (class "Default")
      (node (ref "IC2") (pin "57") (pinfunction "PB5/I2C1_SMBA/SPI1_MOSI/SPI3_MOSI/I2S3_SD_57") (pintype "bidirectional"))
      (node (ref "R17") (pin "1") (pinfunction "1_1") (pintype "passive"))
    )
    (net (code "41") (name "LED_X_RANGE_R") (class "Default")
      (node (ref "IC2") (pin "56") (pinfunction "PB4/NJTRST/SPI3_MISO/SPI1_MISO_56") (pintype "bidirectional"))
      (node (ref "R15") (pin "1") (pinfunction "1_1") (pintype "passive"))
    )
    (net (code "42") (name "NORMALIZATION_PROBE") (class "Default")
      (node (ref "D3") (pin "3") (pinfunction "AC_3") (pintype "passive"))
      (node (ref "IC2") (pin "39") (pinfunction "PC8_39") (pintype "bidirectional"))
      (node (ref "R76") (pin "1") (pinfunction "1_1") (pintype "passive"))
      (node (ref "R77") (pin "1") (pinfunction "1_1") (pintype "passive"))
    )
    (net (code "43") (name "Net-(C5-Pad1)") (class "Default")
      (node (ref "C5") (pin "1") (pinfunction "1_1") (pintype "passive"))
      (node (ref "D1") (pin "C") (pinfunction "C_C") (pintype "passive"))
      (node (ref "L1") (pin "1") (pinfunction "1_1") (pintype "passive"))
      (node (ref "L2") (pin "2") (pinfunction "2_2") (pintype "passive"))
      (node (ref "L3") (pin "2") (pinfunction "2_2") (pintype "passive"))
    )
    (net (code "44") (name "Net-(C6-Pad2)") (class "Default")
      (node (ref "C6") (pin "2") (pinfunction "2_2") (pintype "passive"))
      (node (ref "Q1") (pin "1") (pinfunction "1_1") (pintype "passive"))
      (node (ref "R7") (pin "2") (pinfunction "2_2") (pintype "passive"))
    )
    (net (code "45") (name "Net-(D1-PadA)") (class "Default")
      (node (ref "D1") (pin "A") (pinfunction "A_A") (pintype "passive"))
      (node (ref "JP4") (pin "10") (pinfunction "10_10") (pintype "passive"))
      (node (ref "JP4") (pin "9") (pinfunction "9_9") (pintype "passive"))
    )
    (net (code "46") (name "Net-(D2-PadA)") (class "Default")
      (node (ref "D2") (pin "A") (pinfunction "A_A") (pintype "passive"))
      (node (ref "L4") (pin "2") (pinfunction "2_2") (pintype "passive"))
    )
    (net (code "47") (name "Net-(D2-PadC)") (class "Default")
      (node (ref "D2") (pin "C") (pinfunction "C_C") (pintype "passive"))
      (node (ref "JP4") (pin "1") (pinfunction "1_1") (pintype "passive"))
      (node (ref "JP4") (pin "2") (pinfunction "2_2") (pintype "passive"))
    )
    (net (code "48") (name "Net-(D4-PadC)") (class "Default")
      (node (ref "D4") (pin "C") (pinfunction "C_C") (pintype "passive"))
      (node (ref "Q2") (pin "B") (pinfunction "B_B") (pintype "passive"))
      (node (ref "R24") (pin "2") (pinfunction "2_2") (pintype "passive"))
      (node (ref "R26") (pin "2") (pinfunction "2_2") (pintype "passive"))
    )
    (net (code "49") (name "Net-(D5-PadC)") (class "Default")
      (node (ref "D5") (pin "C") (pinfunction "C_C") (pintype "passive"))
      (node (ref "Q3") (pin "B") (pinfunction "B_B") (pintype "passive"))
      (node (ref "R25") (pin "2") (pinfunction "2_2") (pintype "passive"))
      (node (ref "R27") (pin "2") (pinfunction "2_2") (pintype "passive"))
    )
    (net (code "50") (name "Net-(IC1-VI)") (class "Default")
      (node (ref "C3") (pin "1") (pinfunction "1_1") (pintype "passive"))
      (node (ref "IC1") (pin "1") (pinfunction "VI_1") (pintype "input"))
      (node (ref "L1") (pin "2") (pinfunction "2_2") (pintype "passive"))
    )
    (net (code "51") (name "Net-(IC2-PD0{slash}OSC_IN)") (class "Default")
      (node (ref "IC2") (pin "5") (pinfunction "PD0/OSC_IN_5") (pintype "bidirectional"))
      (node (ref "R8") (pin "1") (pinfunction "1_1") (pintype "passive"))
    )
    (net (code "52") (name "Net-(IC2-PD1{slash}OSC_OUT)") (class "Default")
      (node (ref "IC2") (pin "6") (pinfunction "PD1/OSC_OUT_6") (pintype "bidirectional"))
      (node (ref "R7") (pin "1") (pinfunction "1_1") (pintype "passive"))
    )
    (net (code "53") (name "Net-(IC2-VCAP_1)") (class "Default")
      (node (ref "C15") (pin "1") (pinfunction "1_1") (pintype "passive"))
      (node (ref "IC2") (pin "31") (pinfunction "VCAP_1_31") (pintype "power_in"))
    )
    (net (code "54") (name "Net-(IC2-VCAP_2)") (class "Default")
      (node (ref "C20") (pin "1") (pinfunction "1_1") (pintype "passive"))
      (node (ref "IC2") (pin "47") (pinfunction "VCAP_2_47") (pintype "power_in"))
    )
    (net (code "55") (name "Net-(IC3-VI)") (class "Default")
      (node (ref "C14") (pin "1") (pinfunction "1_1") (pintype "passive"))
      (node (ref "IC3") (pin "3") (pinfunction "VI_3") (pintype "input"))
      (node (ref "L3") (pin "1") (pinfunction "1_1") (pintype "passive"))
    )
    (net (code "56") (name "Net-(IC5A--IN)") (class "Default")
      (node (ref "C40") (pin "1") (pinfunction "1_1") (pintype "passive"))
      (node (ref "IC5") (pin "2") (pinfunction "-IN_2") (pintype "input"))
      (node (ref "R57") (pin "2") (pinfunction "2_2") (pintype "passive"))
      (node (ref "R64") (pin "1") (pinfunction "1_1") (pintype "passive"))
      (node (ref "R70") (pin "1") (pinfunction "1_1") (pintype "passive"))
    )
    (net (code "57") (name "Net-(IC5C--IN)") (class "Default")
      (node (ref "C31") (pin "1") (pinfunction "1_1") (pintype "passive"))
      (node (ref "IC5") (pin "9") (pinfunction "-IN_9") (pintype "input"))
      (node (ref "R28") (pin "1") (pinfunction "1_1") (pintype "passive"))
      (node (ref "R34") (pin "1") (pinfunction "1_1") (pintype "passive"))
      (node (ref "R40") (pin "2") (pinfunction "2_2") (pintype "passive"))
    )
    (net (code "58") (name "Net-(IC5D--IN)") (class "Default")
      (node (ref "C30") (pin "1") (pinfunction "1_1") (pintype "passive"))
      (node (ref "IC5") (pin "13") (pinfunction "-IN_13") (pintype "input"))
      (node (ref "R30") (pin "1") (pinfunction "1_1") (pintype "passive"))
      (node (ref "R33") (pin "1") (pinfunction "1_1") (pintype "passive"))
      (node (ref "R39") (pin "2") (pinfunction "2_2") (pintype "passive"))
    )
    (net (code "59") (name "Net-(IC6A--IN)") (class "Default")
      (node (ref "C41") (pin "1") (pinfunction "1_1") (pintype "passive"))
      (node (ref "IC6") (pin "2") (pinfunction "-IN_2") (pintype "input"))
      (node (ref "R58") (pin "2") (pinfunction "2_2") (pintype "passive"))
      (node (ref "R65") (pin "1") (pinfunction "1_1") (pintype "passive"))
      (node (ref "R71") (pin "1") (pinfunction "1_1") (pintype "passive"))
    )
    (net (code "60") (name "Net-(IC6B--IN)") (class "Default")
      (node (ref "C42") (pin "1") (pinfunction "1_1") (pintype "passive"))
      (node (ref "IC6") (pin "6") (pinfunction "-IN_6") (pintype "input"))
      (node (ref "R59") (pin "2") (pinfunction "2_2") (pintype "passive"))
      (node (ref "R66") (pin "1") (pinfunction "1_1") (pintype "passive"))
      (node (ref "R72") (pin "1") (pinfunction "1_1") (pintype "passive"))
    )
    (net (code "61") (name "Net-(IC6C--IN)") (class "Default")
      (node (ref "C33") (pin "1") (pinfunction "1_1") (pintype "passive"))
      (node (ref "IC6") (pin "9") (pinfunction "-IN_9") (pintype "input"))
      (node (ref "R31") (pin "1") (pinfunction "1_1") (pintype "passive"))
      (node (ref "R32") (pin "1") (pinfunction "1_1") (pintype "passive"))
      (node (ref "R42") (pin "2") (pinfunction "2_2") (pintype "passive"))
    )
    (net (code "62") (name "Net-(IC6D--IN)") (class "Default")
      (node (ref "C32") (pin "1") (pinfunction "1_1") (pintype "passive"))
      (node (ref "IC6") (pin "13") (pinfunction "-IN_13") (pintype "input"))
      (node (ref "R29") (pin "1") (pinfunction "1_1") (pintype "passive"))
      (node (ref "R35") (pin "1") (pinfunction "1_1") (pintype "passive"))
      (node (ref "R41") (pin "2") (pinfunction "2_2") (pintype "passive"))
    )
    (net (code "63") (name "Net-(IC7A--IN)") (class "Default")
      (node (ref "C34") (pin "1") (pinfunction "1_1") (pintype "passive"))
      (node (ref "IC7") (pin "2") (pinfunction "-IN_2") (pintype "input"))
      (node (ref "R43") (pin "2") (pinfunction "2_2") (pintype "passive"))
      (node (ref "R47") (pin "1") (pinfunction "1_1") (pintype "passive"))
    )
    (net (code "64") (name "Net-(IC7B--IN)") (class "Default")
      (node (ref "C43") (pin "1") (pinfunction "1_1") (pintype "passive"))
      (node (ref "IC7") (pin "6") (pinfunction "-IN_6") (pintype "input"))
      (node (ref "R54") (pin "1") (pinfunction "1_1") (pintype "passive"))
      (node (ref "R60") (pin "2") (pinfunction "2_2") (pintype "passive"))
    )
    (net (code "65") (name "Net-(IC7C--IN)") (class "Default")
      (node (ref "C44") (pin "1") (pinfunction "1_1") (pintype "passive"))
      (node (ref "IC7") (pin "9") (pinfunction "-IN_9") (pintype "input"))
      (node (ref "R53") (pin "1") (pinfunction "1_1") (pintype "passive"))
      (node (ref "R61") (pin "2") (pinfunction "2_2") (pintype "passive"))
    )
    (net (code "66") (name "Net-(IC7D--IN)") (class "Default")
      (node (ref "C35") (pin "1") (pinfunction "1_1") (pintype "passive"))
      (node (ref "IC7") (pin "13") (pinfunction "-IN_13") (pintype "input"))
      (node (ref "R44") (pin "2") (pinfunction "2_2") (pintype "passive"))
      (node (ref "R48") (pin "1") (pinfunction "1_1") (pintype "passive"))
    )
    (net (code "67") (name "Net-(IC9A-+IN)") (class "Default")
      (node (ref "IC9") (pin "3") (pinfunction "+IN_3") (pintype "input"))
      (node (ref "R56") (pin "1") (pinfunction "1_1") (pintype "passive"))
    )
    (net (code "68") (name "Net-(IC9A--IN)") (class "Default")
      (node (ref "IC9") (pin "2") (pinfunction "-IN_2") (pintype "input"))
      (node (ref "R50") (pin "1") (pinfunction "1_1") (pintype "passive"))
      (node (ref "R51") (pin "2") (pinfunction "2_2") (pintype "passive"))
    )
    (net (code "69") (name "Net-(IC9A-OUT)") (class "Default")
      (node (ref "IC9") (pin "1") (pinfunction "OUT_1") (pintype "output"))
      (node (ref "R51") (pin "1") (pinfunction "1_1") (pintype "passive"))
      (node (ref "R85") (pin "2") (pinfunction "2_2") (pintype "passive"))
    )
    (net (code "70") (name "Net-(IC9B--IN)") (class "Default")
      (node (ref "IC9") (pin "6") (pinfunction "-IN_6") (pintype "input"))
      (node (ref "IC9") (pin "7") (pinfunction "OUT_7") (pintype "output"))
    )
    (net (code "71") (name "Net-(IC9C-+IN)") (class "Default")
      (node (ref "IC9") (pin "10") (pinfunction "+IN_10") (pintype "input"))
      (node (ref "R67") (pin "1") (pinfunction "1_1") (pintype "passive"))
    )
    (net (code "72") (name "Net-(IC9C--IN)") (class "Default")
      (node (ref "IC9") (pin "9") (pinfunction "-IN_9") (pintype "input"))
      (node (ref "R69") (pin "2") (pinfunction "2_2") (pintype "passive"))
      (node (ref "R75") (pin "1") (pinfunction "1_1") (pintype "passive"))
    )
    (net (code "73") (name "Net-(IC9C-OUT)") (class "Default")
      (node (ref "IC9") (pin "8") (pinfunction "OUT_8") (pintype "output"))
      (node (ref "R69") (pin "1") (pinfunction "1_1") (pintype "passive"))
      (node (ref "R87") (pin "2") (pinfunction "2_2") (pintype "passive"))
    )
    (net (code "74") (name "Net-(IC9D-+IN)") (class "Default")
      (node (ref "IC9") (pin "12") (pinfunction "+IN_12") (pintype "input"))
      (node (ref "R55") (pin "1") (pinfunction "1_1") (pintype "passive"))
    )
    (net (code "75") (name "Net-(IC9D--IN)") (class "Default")
      (node (ref "IC9") (pin "13") (pinfunction "-IN_13") (pintype "input"))
      (node (ref "R49") (pin "1") (pinfunction "1_1") (pintype "passive"))
      (node (ref "R52") (pin "2") (pinfunction "2_2") (pintype "passive"))
    )
    (net (code "76") (name "Net-(IC9D-OUT)") (class "Default")
      (node (ref "IC9") (pin "14") (pinfunction "OUT_14") (pintype "output"))
      (node (ref "R52") (pin "1") (pinfunction "1_1") (pintype "passive"))
      (node (ref "R86") (pin "2") (pinfunction "2_2") (pintype "passive"))
    )
    (net (code "77") (name "Net-(IC10A-+IN)") (class "Default")
      (node (ref "C34") (pin "2") (pinfunction "2_2") (pintype "passive"))
      (node (ref "IC10") (pin "3") (pinfunction "+IN_3") (pintype "input"))
      (node (ref "IC7") (pin "1") (pinfunction "OUT_1") (pintype "output"))
      (node (ref "R45") (pin "2") (pinfunction "2_2") (pintype "passive"))
    )
    (net (code "78") (name "Net-(IC10A--IN)") (class "Default")
      (node (ref "IC10") (pin "2") (pinfunction "-IN_2") (pintype "input"))
      (node (ref "LED10") (pin "2") (pinfunction "2_2") (pintype "bidirectional"))
      (node (ref "R79") (pin "1") (pinfunction "1_1") (pintype "passive"))
    )
    (net (code "79") (name "Net-(IC10A-OUT)") (class "Default")
      (node (ref "IC10") (pin "1") (pinfunction "OUT_1") (pintype "output"))
      (node (ref "LED10") (pin "1") (pinfunction "1_1") (pintype "bidirectional"))
    )
    (net (code "80") (name "Net-(IC10B-+IN)") (class "Default")
      (node (ref "C43") (pin "2") (pinfunction "2_2") (pintype "passive"))
      (node (ref "IC10") (pin "5") (pinfunction "+IN_5") (pintype "input"))
      (node (ref "IC7") (pin "7") (pinfunction "OUT_7") (pintype "output"))
      (node (ref "R62") (pin "2") (pinfunction "2_2") (pintype "passive"))
    )
    (net (code "81") (name "Net-(IC10B--IN)") (class "Default")
      (node (ref "IC10") (pin "6") (pinfunction "-IN_6") (pintype "input"))
      (node (ref "LED9") (pin "2") (pinfunction "2_2") (pintype "bidirectional"))
      (node (ref "R78") (pin "1") (pinfunction "1_1") (pintype "passive"))
    )
    (net (code "82") (name "Net-(IC10B-OUT)") (class "Default")
      (node (ref "IC10") (pin "7") (pinfunction "OUT_7") (pintype "output"))
      (node (ref "LED9") (pin "1") (pinfunction "1_1") (pintype "bidirectional"))
    )
    (net (code "83") (name "Net-(IC10C-+IN)") (class "Default")
      (node (ref "C44") (pin "2") (pinfunction "2_2") (pintype "passive"))
      (node (ref "IC10") (pin "10") (pinfunction "+IN_10") (pintype "input"))
      (node (ref "IC7") (pin "8") (pinfunction "OUT_8") (pintype "output"))
      (node (ref "R63") (pin "2") (pinfunction "2_2") (pintype "passive"))
    )
    (net (code "84") (name "Net-(IC10C--IN)") (class "Default")
      (node (ref "IC10") (pin "9") (pinfunction "-IN_9") (pintype "input"))
      (node (ref "LED12") (pin "2") (pinfunction "2_2") (pintype "bidirectional"))
      (node (ref "R81") (pin "1") (pinfunction "1_1") (pintype "passive"))
    )
    (net (code "85") (name "Net-(IC10C-OUT)") (class "Default")
      (node (ref "IC10") (pin "8") (pinfunction "OUT_8") (pintype "output"))
      (node (ref "LED12") (pin "1") (pinfunction "1_1") (pintype "bidirectional"))
    )
    (net (code "86") (name "Net-(IC10D-+IN)") (class "Default")
      (node (ref "C35") (pin "2") (pinfunction "2_2") (pintype "passive"))
      (node (ref "IC10") (pin "12") (pinfunction "+IN_12") (pintype "input"))
      (node (ref "IC7") (pin "14") (pinfunction "OUT_14") (pintype "output"))
      (node (ref "R46") (pin "2") (pinfunction "2_2") (pintype "passive"))
    )
    (net (code "87") (name "Net-(IC10D--IN)") (class "Default")
      (node (ref "IC10") (pin "13") (pinfunction "-IN_13") (pintype "input"))
      (node (ref "LED11") (pin "2") (pinfunction "2_2") (pintype "bidirectional"))
      (node (ref "R80") (pin "1") (pinfunction "1_1") (pintype "passive"))
    )
    (net (code "88") (name "Net-(IC10D-OUT)") (class "Default")
      (node (ref "IC10") (pin "14") (pinfunction "OUT_14") (pintype "output"))
      (node (ref "LED11") (pin "1") (pinfunction "1_1") (pintype "bidirectional"))
    )
    (net (code "89") (name "Net-(J1-3)") (class "Default")
      (node (ref "C53") (pin "1") (pinfunction "1_1") (pintype "passive"))
      (node (ref "J1") (pin "P3") (pinfunction "3_P3") (pintype "passive"))
      (node (ref "R64") (pin "2") (pinfunction "2_2") (pintype "passive"))
    )
    (net (code "90") (name "Net-(J2-3)") (class "Default")
      (node (ref "C45") (pin "1") (pinfunction "1_1") (pintype "passive"))
      (node (ref "J2") (pin "P3") (pinfunction "3_P3") (pintype "passive"))
      (node (ref "R33") (pin "2") (pinfunction "2_2") (pintype "passive"))
    )
    (net (code "91") (name "Net-(J3-2)") (class "Default")
      (node (ref "J3") (pin "P2") (pinfunction "2_P2") (pintype "passive"))
      (node (ref "R76") (pin "2") (pinfunction "2_2") (pintype "passive"))
    )
    (net (code "92") (name "Net-(J3-3)") (class "Default")
      (node (ref "J3") (pin "P3") (pinfunction "3_P3") (pintype "passive"))
      (node (ref "R26") (pin "1") (pinfunction "1_1") (pintype "passive"))
    )
    (net (code "93") (name "Net-(J4-3)") (class "Default")
      (node (ref "C56") (pin "1") (pinfunction "1_1") (pintype "passive"))
      (node (ref "J4") (pin "P3") (pinfunction "3_P3") (pintype "passive"))
      (node (ref "R65") (pin "2") (pinfunction "2_2") (pintype "passive"))
    )
    (net (code "94") (name "Net-(J5-3)") (class "Default")
      (node (ref "C58") (pin "1") (pinfunction "1_1") (pintype "passive"))
      (node (ref "J5") (pin "P3") (pinfunction "3_P3") (pintype "passive"))
      (node (ref "R66") (pin "2") (pinfunction "2_2") (pintype "passive"))
    )
    (net (code "95") (name "Net-(J6-3)") (class "Default")
      (node (ref "C54") (pin "1") (pinfunction "1_1") (pintype "passive"))
      (node (ref "J6") (pin "P3") (pinfunction "3_P3") (pintype "passive"))
      (node (ref "R32") (pin "2") (pinfunction "2_2") (pintype "passive"))
    )
    (net (code "96") (name "Net-(J7-3)") (class "Default")
      (node (ref "C55") (pin "1") (pinfunction "1_1") (pintype "passive"))
      (node (ref "J7") (pin "P3") (pinfunction "3_P3") (pintype "passive"))
      (node (ref "R35") (pin "2") (pinfunction "2_2") (pintype "passive"))
    )
    (net (code "97") (name "Net-(J8-3)") (class "Default")
      (node (ref "C57") (pin "1") (pinfunction "1_1") (pintype "passive"))
      (node (ref "J8") (pin "P3") (pinfunction "3_P3") (pintype "passive"))
      (node (ref "R34") (pin "2") (pinfunction "2_2") (pintype "passive"))
    )
    (net (code "98") (name "Net-(J9-2)") (class "Default")
      (node (ref "J9") (pin "P2") (pinfunction "2_P2") (pintype "passive"))
      (node (ref "R77") (pin "2") (pinfunction "2_2") (pintype "passive"))
    )
    (net (code "99") (name "Net-(J9-3)") (class "Default")
      (node (ref "J9") (pin "P3") (pinfunction "3_P3") (pintype "passive"))
      (node (ref "R27") (pin "1") (pinfunction "1_1") (pintype "passive"))
    )
    (net (code "100") (name "Net-(J10-3)") (class "Default")
      (node (ref "J10") (pin "P3") (pinfunction "3_P3") (pintype "passive"))
      (node (ref "R85") (pin "1") (pinfunction "1_1") (pintype "passive"))
    )
    (net (code "101") (name "Net-(J11-3)") (class "Default")
      (node (ref "J11") (pin "P3") (pinfunction "3_P3") (pintype "passive"))
      (node (ref "R86") (pin "1") (pinfunction "1_1") (pintype "passive"))
    )
    (net (code "102") (name "Net-(J12-3)") (class "Default")
      (node (ref "J12") (pin "P3") (pinfunction "3_P3") (pintype "passive"))
      (node (ref "R87") (pin "1") (pinfunction "1_1") (pintype "passive"))
    )
    (net (code "103") (name "Net-(J13-3)") (class "Default")
      (node (ref "J13") (pin "P3") (pinfunction "3_P3") (pintype "passive"))
      (node (ref "R60") (pin "1") (pinfunction "1_1") (pintype "passive"))
      (node (ref "R62") (pin "1") (pinfunction "1_1") (pintype "passive"))
    )
    (net (code "104") (name "Net-(J14-3)") (class "Default")
      (node (ref "J14") (pin "P3") (pinfunction "3_P3") (pintype "passive"))
      (node (ref "R43") (pin "1") (pinfunction "1_1") (pintype "passive"))
      (node (ref "R45") (pin "1") (pinfunction "1_1") (pintype "passive"))
    )
    (net (code "105") (name "Net-(J15-3)") (class "Default")
      (node (ref "J15") (pin "P3") (pinfunction "3_P3") (pintype "passive"))
      (node (ref "R44") (pin "1") (pinfunction "1_1") (pintype "passive"))
      (node (ref "R46") (pin "1") (pinfunction "1_1") (pintype "passive"))
    )
    (net (code "106") (name "Net-(J16-3)") (class "Default")
      (node (ref "J16") (pin "P3") (pinfunction "3_P3") (pintype "passive"))
      (node (ref "R61") (pin "1") (pinfunction "1_1") (pintype "passive"))
      (node (ref "R63") (pin "1") (pinfunction "1_1") (pintype "passive"))
    )
    (net (code "107") (name "Net-(JP2-Pad1)") (class "Default")
      (node (ref "JP2") (pin "1") (pinfunction "1_1") (pintype "passive"))
      (node (ref "R3") (pin "1") (pinfunction "1_1") (pintype "passive"))
    )
    (net (code "108") (name "Net-(JP2-Pad2)") (class "Default")
      (node (ref "JP2") (pin "2") (pinfunction "2_2") (pintype "passive"))
      (node (ref "R2") (pin "1") (pinfunction "1_1") (pintype "passive"))
    )
    (net (code "109") (name "Net-(LED1-GRN)") (class "Default")
      (node (ref "LED1") (pin "1") (pinfunction "GRN_1") (pintype "bidirectional"))
      (node (ref "R10") (pin "2") (pinfunction "2_2") (pintype "passive"))
    )
    (net (code "110") (name "Net-(LED1-RED)") (class "Default")
      (node (ref "LED1") (pin "3") (pinfunction "RED_3") (pintype "bidirectional"))
      (node (ref "R9") (pin "2") (pinfunction "2_2") (pintype "passive"))
    )
    (net (code "111") (name "Net-(LED2-GRN)") (class "Default")
      (node (ref "LED2") (pin "1") (pinfunction "GRN_1") (pintype "bidirectional"))
      (node (ref "R12") (pin "2") (pinfunction "2_2") (pintype "passive"))
    )
    (net (code "112") (name "Net-(LED2-RED)") (class "Default")
      (node (ref "LED2") (pin "3") (pinfunction "RED_3") (pintype "bidirectional"))
      (node (ref "R11") (pin "2") (pinfunction "2_2") (pintype "passive"))
    )
    (net (code "113") (name "Net-(LED3-GRN)") (class "Default")
      (node (ref "LED3") (pin "1") (pinfunction "GRN_1") (pintype "bidirectional"))
      (node (ref "R18") (pin "2") (pinfunction "2_2") (pintype "passive"))
    )
    (net (code "114") (name "Net-(LED3-RED)") (class "Default")
      (node (ref "LED3") (pin "3") (pinfunction "RED_3") (pintype "bidirectional"))
      (node (ref "R19") (pin "2") (pinfunction "2_2") (pintype "passive"))
    )
    (net (code "115") (name "Net-(LED4-GRN)") (class "Default")
      (node (ref "LED4") (pin "1") (pinfunction "GRN_1") (pintype "bidirectional"))
      (node (ref "R17") (pin "2") (pinfunction "2_2") (pintype "passive"))
    )
    (net (code "116") (name "Net-(LED4-RED)") (class "Default")
      (node (ref "LED4") (pin "3") (pinfunction "RED_3") (pintype "bidirectional"))
      (node (ref "R15") (pin "2") (pinfunction "2_2") (pintype "passive"))
    )
    (net (code "117") (name "Net-(LED5-GRN)") (class "Default")
      (node (ref "LED5") (pin "1") (pinfunction "GRN_1") (pintype "bidirectional"))
      (node (ref "R36") (pin "2") (pinfunction "2_2") (pintype "passive"))
    )
    (net (code "118") (name "Net-(LED6-Pad2)") (class "Default")
      (node (ref "LED6") (pin "2") (pinfunction "2_2") (pintype "bidirectional"))
      (node (ref "R82") (pin "2") (pinfunction "2_2") (pintype "passive"))
    )
    (net (code "119") (name "Net-(LED7-Pad2)") (class "Default")
      (node (ref "LED7") (pin "2") (pinfunction "2_2") (pintype "bidirectional"))
      (node (ref "R83") (pin "2") (pinfunction "2_2") (pintype "passive"))
    )
    (net (code "120") (name "Net-(LED8-Pad2)") (class "Default")
      (node (ref "LED8") (pin "2") (pinfunction "2_2") (pintype "bidirectional"))
      (node (ref "R84") (pin "2") (pinfunction "2_2") (pintype "passive"))
    )
    (net (code "121") (name "Net-(Q1B-2)") (class "Default")
      (node (ref "C4") (pin "2") (pinfunction "2_2") (pintype "passive"))
      (node (ref "Q1") (pin "3") (pinfunction "2_3") (pintype "passive"))
      (node (ref "R8") (pin "2") (pinfunction "2_2") (pintype "passive"))
    )
    (net (code "122") (name "Net-(R1-Pad2)") (class "Default")
      (node (ref "R1") (pin "2") (pinfunction "2_2") (pintype "passive"))
      (node (ref "SW1") (pin "L1") (pinfunction "L1_L1") (pintype "passive"))
    )
    (net (code "123") (name "Net-(R5-Pad2)") (class "Default")
      (node (ref "R5") (pin "2") (pinfunction "2_2") (pintype "passive"))
      (node (ref "SW2") (pin "L1") (pinfunction "L1_L1") (pintype "passive"))
    )
    (net (code "124") (name "RESET") (class "Default")
      (node (ref "C7") (pin "1") (pinfunction "1_1") (pintype "passive"))
      (node (ref "IC2") (pin "7") (pinfunction "NRST_7") (pintype "bidirectional"))
      (node (ref "JP1") (pin "4") (pinfunction "4_4") (pintype "passive"))
      (node (ref "R6") (pin "1") (pinfunction "1_1") (pintype "passive"))
    )
    (net (code "125") (name "RX") (class "Default")
      (node (ref "IC2") (pin "43") (pinfunction "PA10/USART1_RX/TIM1_CH3_43") (pintype "bidirectional"))
      (node (ref "R3") (pin "2") (pinfunction "2_2") (pintype "passive"))
    )
    (net (code "126") (name "SWCLK") (class "Default")
      (node (ref "IC2") (pin "49") (pinfunction "PA14/JTCK-SWCLK_49") (pintype "bidirectional"))
      (node (ref "JP1") (pin "3") (pinfunction "3_3") (pintype "passive"))
    )
    (net (code "127") (name "SWDIO") (class "Default")
      (node (ref "IC2") (pin "46") (pinfunction "PA13/JTMS-SWDAT_46") (pintype "bidirectional"))
      (node (ref "JP1") (pin "2") (pinfunction "2_2") (pintype "passive"))
    )
    (net (code "128") (name "SW_T_DV") (class "Default")
      (node (ref "IC2") (pin "30") (pinfunction "PB11/I2C2_SDA/USART3_RX_30") (pintype "bidirectional"))
      (node (ref "SW1") (pin "P2") (pinfunction "A2_P2") (pintype "passive"))
      (node (ref "SW1") (pin "P5") (pinfunction "B2_P5") (pintype "passive"))
    )
    (net (code "129") (name "SW_T_MODE") (class "Default")
      (node (ref "IC2") (pin "35") (pinfunction "PB14/SPI2_MISO/USART3_RTS/TIM1_CH2N_35") (pintype "bidirectional"))
      (node (ref "SW3") (pin "3") (pinfunction "3_3") (pintype "passive"))
      (node (ref "SW3") (pin "4") (pinfunction "4_4") (pintype "passive"))
    )
    (net (code "130") (name "SW_T_RANGE") (class "Default")
      (node (ref "IC2") (pin "36") (pinfunction "PB15/SPI2_MOSI/I2S2_SD/TIM1_CH3N_36") (pintype "bidirectional"))
      (node (ref "SW5") (pin "3") (pinfunction "3_3") (pintype "passive"))
      (node (ref "SW5") (pin "4") (pinfunction "4_4") (pintype "passive"))
    )
    (net (code "131") (name "SW_X_DV") (class "Default")
      (node (ref "IC2") (pin "4") (pinfunction "PC15/OSC_OUT_4") (pintype "bidirectional"))
      (node (ref "SW2") (pin "P2") (pinfunction "A2_P2") (pintype "passive"))
      (node (ref "SW2") (pin "P5") (pinfunction "B2_P5") (pintype "passive"))
    )
    (net (code "132") (name "SW_X_EXT") (class "Default")
      (node (ref "IC2") (pin "54") (pinfunction "PD2/TIM3-ETR_54") (pintype "bidirectional"))
      (node (ref "SW7") (pin "3") (pinfunction "3_3") (pintype "passive"))
      (node (ref "SW7") (pin "4") (pinfunction "4_4") (pintype "passive"))
    )
    (net (code "133") (name "SW_X_MODE") (class "Default")
      (node (ref "IC2") (pin "2") (pinfunction "PC13-TAMPER-RTC_2") (pintype "bidirectional"))
      (node (ref "SW4") (pin "3") (pinfunction "3_3") (pintype "passive"))
      (node (ref "SW4") (pin "4") (pinfunction "4_4") (pintype "passive"))
    )
    (net (code "134") (name "SW_X_RANGE") (class "Default")
      (node (ref "IC2") (pin "58") (pinfunction "PB6/I2C1_SCL/TIM4_CH1/USART1_TX_58") (pintype "bidirectional"))
      (node (ref "SW6") (pin "3") (pinfunction "3_3") (pintype "passive"))
      (node (ref "SW6") (pin "4") (pinfunction "4_4") (pintype "passive"))
    )
    (net (code "135") (name "TX") (class "Default")
      (node (ref "IC2") (pin "42") (pinfunction "PA9/USART1_TX/TIM1_CH2_42") (pintype "bidirectional"))
      (node (ref "R2") (pin "2") (pinfunction "2_2") (pintype "passive"))
    )
    (net (code "136") (name "T_CLOCK") (class "Default")
      (node (ref "IC2") (pin "40") (pinfunction "PC9/I2S2_CKIN/I2S3_CKIN_40") (pintype "bidirectional"))
      (node (ref "Q2") (pin "C") (pinfunction "C_C") (pintype "passive"))
      (node (ref "R22") (pin "1") (pinfunction "1_1") (pintype "passive"))
    )
    (net (code "137") (name "VCC") (class "Default")
      (node (ref "C11") (pin "+") (pinfunction "+_+") (pintype "passive"))
      (node (ref "C39") (pin "1") (pinfunction "1_1") (pintype "passive"))
      (node (ref "C48") (pin "1") (pinfunction "1_1") (pintype "passive"))
      (node (ref "C50") (pin "1") (pinfunction "1_1") (pintype "passive"))
      (node (ref "IC10") (pin "4") (pinfunction "V+_4") (pintype "power_in"))
      (node (ref "IC7") (pin "4") (pinfunction "V+_4") (pintype "power_in"))
      (node (ref "IC9") (pin "4") (pinfunction "V+_4") (pintype "power_in"))
      (node (ref "L2") (pin "1") (pinfunction "1_1") (pintype "passive"))
    )
    (net (code "138") (name "VEE") (class "Default")
      (node (ref "C22") (pin "-") (pinfunction "-_-") (pintype "passive"))
      (node (ref "C37") (pin "2") (pinfunction "2_2") (pintype "passive"))
      (node (ref "C49") (pin "2") (pinfunction "2_2") (pintype "passive"))
      (node (ref "IC10") (pin "11") (pinfunction "V-_11") (pintype "power_in"))
      (node (ref "IC7") (pin "11") (pinfunction "V-_11") (pintype "power_in"))
      (node (ref "L4") (pin "1") (pinfunction "1_1") (pintype "passive"))
      (node (ref "R68") (pin "1") (pinfunction "1_1") (pintype "passive"))
    )
    (net (code "139") (name "VREF") (class "Default")
      (node (ref "C25") (pin "1") (pinfunction "1_1") (pintype "passive"))
      (node (ref "IC4") (pin "3") (pinfunction "VREFH_3") (pintype "bidirectional"))
      (node (ref "R74") (pin "2") (pinfunction "2_2") (pintype "passive"))
    )
    (net (code "140") (name "VREF_BIAS") (class "Default")
      (node (ref "C51") (pin "1") (pinfunction "1_1") (pintype "passive"))
      (node (ref "IC7") (pin "10") (pinfunction "+IN_10") (pintype "input"))
      (node (ref "IC7") (pin "12") (pinfunction "+IN_12") (pintype "input"))
      (node (ref "IC7") (pin "3") (pinfunction "+IN_3") (pintype "input"))
      (node (ref "IC7") (pin "5") (pinfunction "+IN_5") (pintype "input"))
      (node (ref "R73") (pin "2") (pinfunction "2_2") (pintype "passive"))
      (node (ref "R74") (pin "1") (pinfunction "1_1") (pintype "passive"))
    )
    (net (code "141") (name "X_CLOCK") (class "Default")
      (node (ref "IC2") (pin "41") (pinfunction "PA8/USART1_CK/TIM1_CH1/MCO_41") (pintype "bidirectional"))
      (node (ref "Q3") (pin "C") (pinfunction "C_C") (pintype "passive"))
      (node (ref "R23") (pin "1") (pinfunction "1_1") (pintype "passive"))
    )
    (net (code "142") (name "unconnected-(IC2-PC14{slash}OSC32_IN-Pad3)") (class "Default")
      (node (ref "IC2") (pin "3") (pinfunction "PC14/OSC32_IN_3") (pintype "bidirectional"))
    )
    (net (code "143") (name "unconnected-(J10-2-PadP2)") (class "Default")
      (node (ref "J10") (pin "P2") (pinfunction "2_P2") (pintype "passive"))
    )
    (net (code "144") (name "unconnected-(J11-2-PadP2)") (class "Default")
      (node (ref "J11") (pin "P2") (pinfunction "2_P2") (pintype "passive"))
    )
    (net (code "145") (name "unconnected-(J12-2-PadP2)") (class "Default")
      (node (ref "J12") (pin "P2") (pinfunction "2_P2") (pintype "passive"))
    )
    (net (code "146") (name "unconnected-(J13-2-PadP2)") (class "Default")
      (node (ref "J13") (pin "P2") (pinfunction "2_P2") (pintype "passive"))
    )
    (net (code "147") (name "unconnected-(J14-2-PadP2)") (class "Default")
      (node (ref "J14") (pin "P2") (pinfunction "2_P2") (pintype "passive"))
    )
    (net (code "148") (name "unconnected-(J15-2-PadP2)") (class "Default")
      (node (ref "J15") (pin "P2") (pinfunction "2_P2") (pintype "passive"))
    )
    (net (code "149") (name "unconnected-(J16-2-PadP2)") (class "Default")
      (node (ref "J16") (pin "P2") (pinfunction "2_P2") (pintype "passive"))
    )
    (net (code "150") (name "unconnected-(LED5-RED-Pad3)") (class "Default")
      (node (ref "LED5") (pin "3") (pinfunction "RED_3") (pintype "bidirectional"))
    )
    (net (code "151") (name "unconnected-(SW1A-A1-PadP1)") (class "Default")
      (node (ref "SW1") (pin "P1") (pinfunction "A1_P1") (pintype "passive"))
    )
    (net (code "152") (name "unconnected-(SW1A-B1-PadP4)") (class "Default")
      (node (ref "SW1") (pin "P4") (pinfunction "B1_P4") (pintype "passive"))
    )
    (net (code "153") (name "unconnected-(SW2A-A1-PadP1)") (class "Default")
      (node (ref "SW2") (pin "P1") (pinfunction "A1_P1") (pintype "passive"))
    )
    (net (code "154") (name "unconnected-(SW2A-B1-PadP4)") (class "Default")
      (node (ref "SW2") (pin "P4") (pinfunction "B1_P4") (pintype "passive"))
    )
  )
)
